# PwrAndBias.net
KiCad netlist of a schematic drawn in Altium Designer
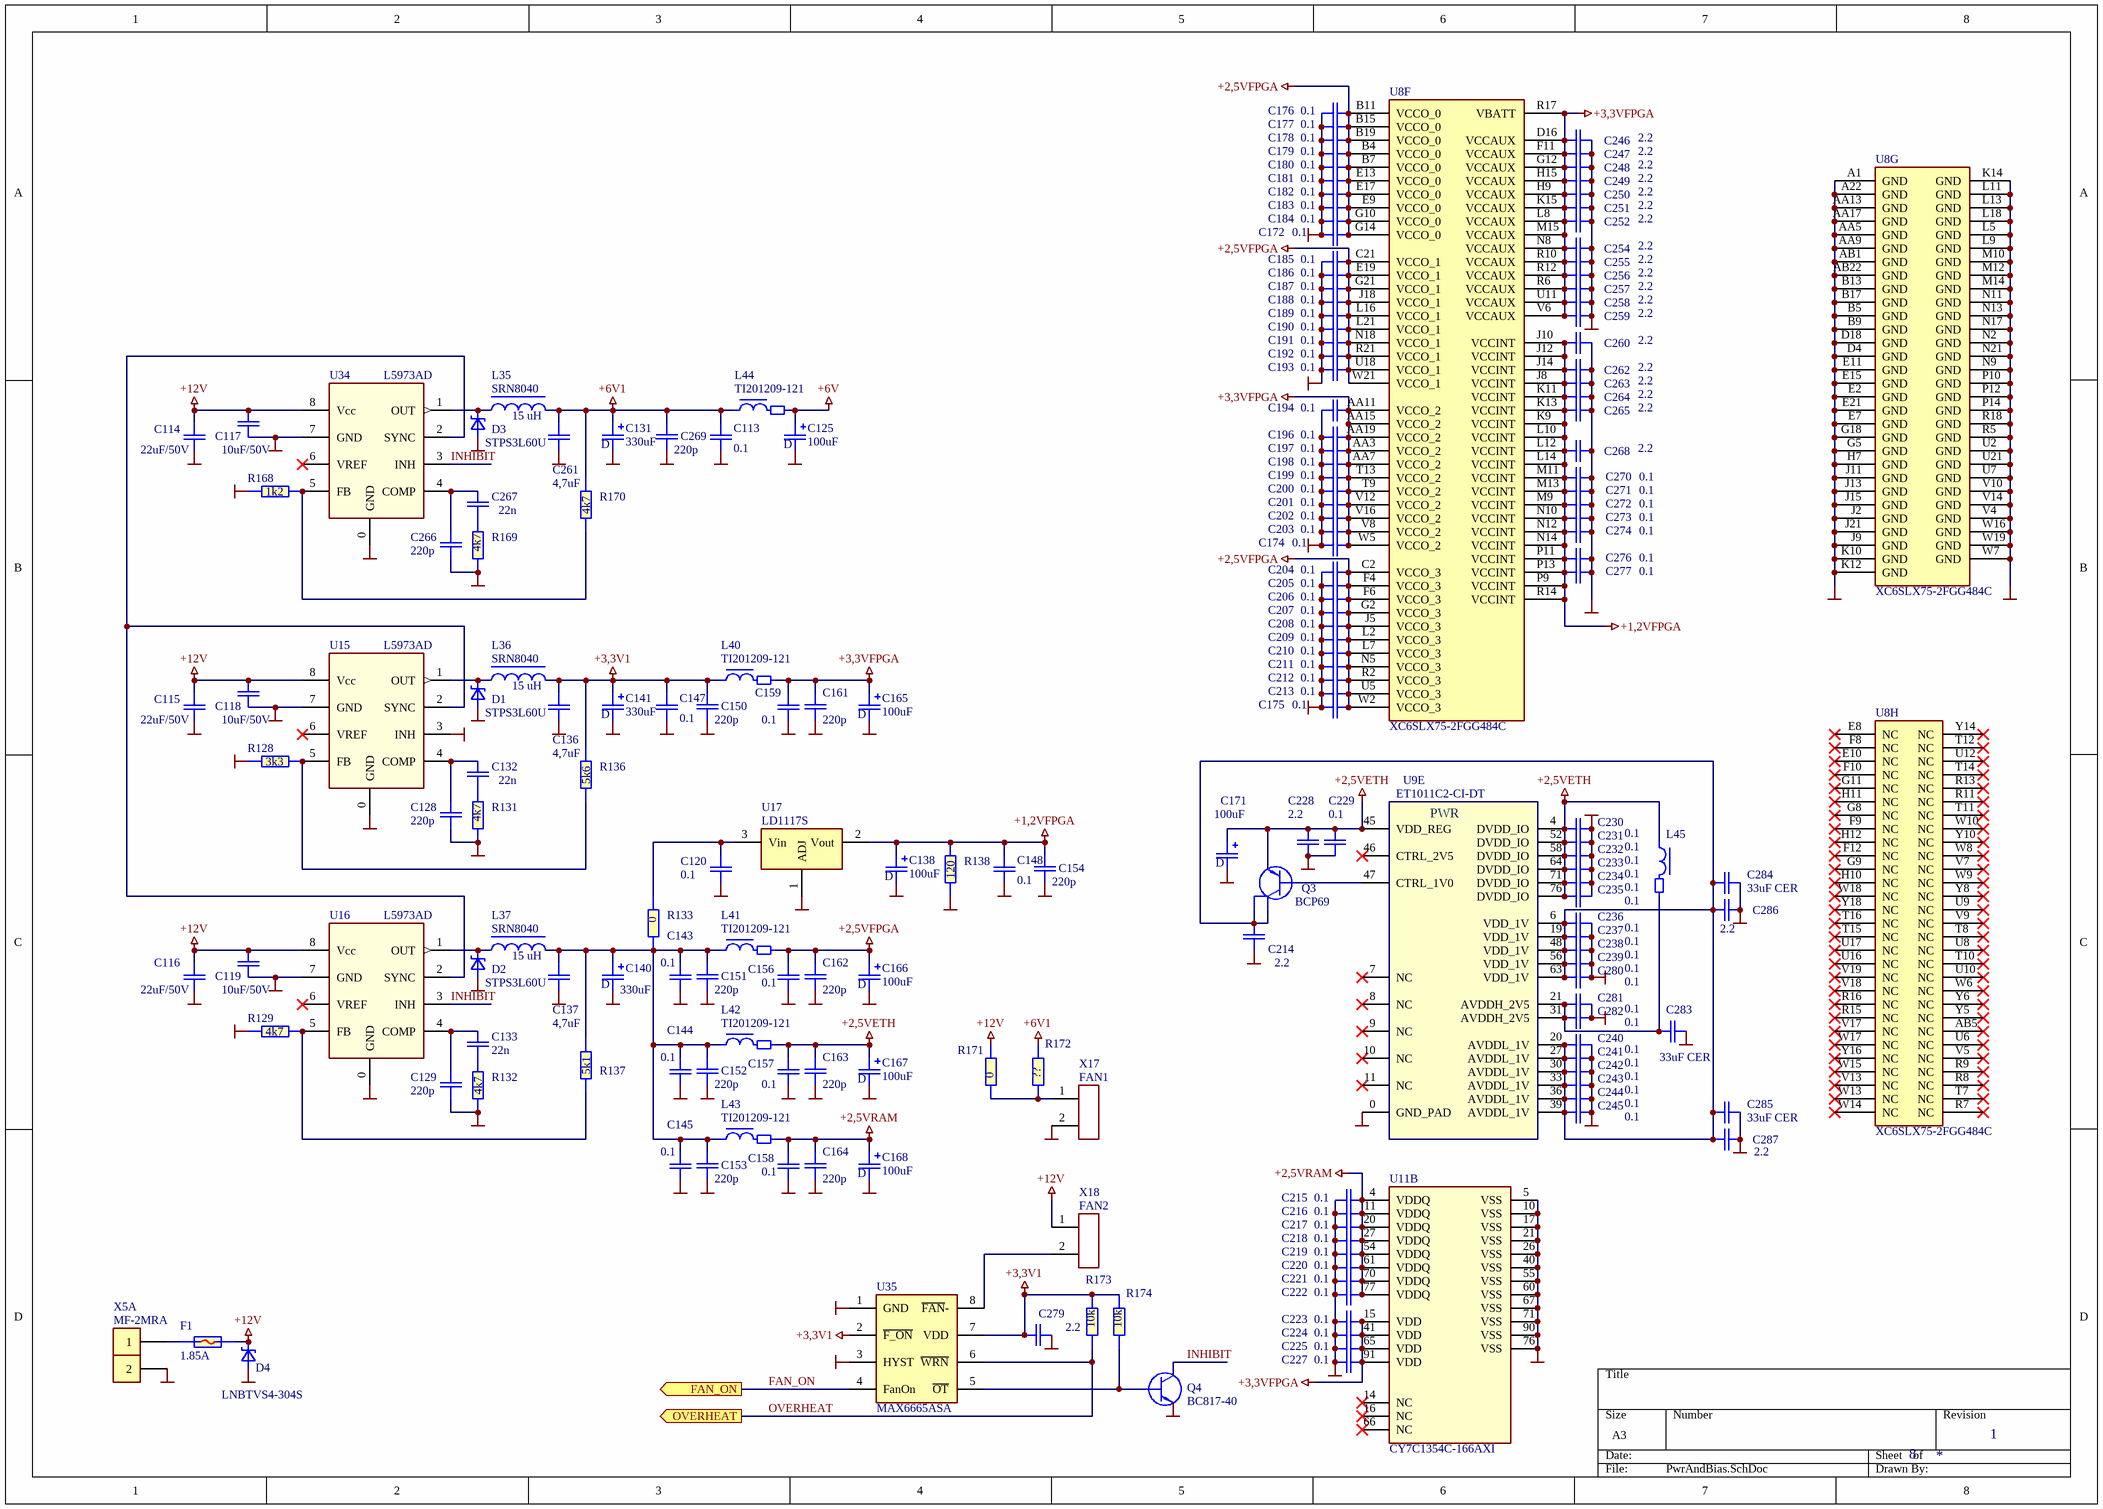
[diagram p0: PwrAndBias.SchDoc]

(export (version "E")
  (design (tool "Eeschema 10.0.6"))
  (components
    (comp (ref "C113")
      (value "0.1")
      (footprint "C0402-Phillips")
      (description "Конденсатор")
      (fields (field (name "MANUFACTURER") "MURATA") (field (name "TOLERANCE") "20%"))
      (libsource (lib "Capacitors") (part "C0402"))
    )
    (comp (ref "C114")
      (value "22uF/50V")
      (footprint "C2220")
      (description "Конденсатор")
      (fields (field (name "MANUFACTURER") "TDK"))
      (libsource (lib "Capacitors") (part "C2220"))
    )
    (comp (ref "C115")
      (value "22uF/50V")
      (footprint "C2220")
      (description "Конденсатор")
      (fields (field (name "MANUFACTURER") "TDK"))
      (libsource (lib "Capacitors") (part "C2220"))
    )
    (comp (ref "C116")
      (value "22uF/50V")
      (footprint "C2220")
      (description "Конденсатор")
      (fields (field (name "MANUFACTURER") "TDK"))
      (libsource (lib "Capacitors") (part "C2220"))
    )
    (comp (ref "C117")
      (value "10uF/50V")
      (footprint "C1210_H2,5")
      (description "Конденсатор")
      (fields (field (name "MANUFACTURER") "TAIYO YUDEN") (field (name "TOLERANCE") "20%"))
      (libsource (lib "Andy") (part "C1210_H2,5"))
    )
    (comp (ref "C118")
      (value "10uF/50V")
      (footprint "C1210_H2,5")
      (description "Конденсатор")
      (fields (field (name "MANUFACTURER") "TAIYO YUDEN") (field (name "TOLERANCE") "20%"))
      (libsource (lib "Andy") (part "C1210_H2,5"))
    )
    (comp (ref "C119")
      (value "10uF/50V")
      (footprint "C1210_H2,5")
      (description "Конденсатор")
      (fields (field (name "MANUFACTURER") "TAIYO YUDEN") (field (name "TOLERANCE") "20%"))
      (libsource (lib "Andy") (part "C1210_H2,5"))
    )
    (comp (ref "C120")
      (value "0.1")
      (footprint "C0402-Phillips")
      (description "Конденсатор")
      (fields (field (name "MANUFACTURER") "MURATA") (field (name "TOLERANCE") "20%"))
      (libsource (lib "Capacitors") (part "C0402"))
    )
    (comp (ref "C125")
      (value "100uF")
      (footprint "cd7343")
      (description "Конденсатор")
      (fields (field (name "MANUFACTURER") "SPRAGUE"))
      (libsource (lib "altium-import") (part "root_0_CD7343_"))
    )
    (comp (ref "C128")
      (value "220p")
      (footprint "C0603-PHILLIPS")
      (description "Конденсатор")
      (fields (field (name "MANUFACTURER") "MURATA") (field (name "TOLERANCE") "20%"))
      (libsource (lib "altium-import") (part "root_0_C0603_"))
    )
    (comp (ref "C129")
      (value "220p")
      (footprint "C0603-PHILLIPS")
      (description "Конденсатор")
      (fields (field (name "MANUFACTURER") "MURATA") (field (name "TOLERANCE") "20%"))
      (libsource (lib "altium-import") (part "root_0_C0603_"))
    )
    (comp (ref "C131")
      (value "330uF")
      (footprint "cd7343")
      (description "Конденсатор")
      (fields (field (name "MANUFACTURER") "Kemet"))
      (libsource (lib "altium-import") (part "root_0_CD7343_"))
    )
    (comp (ref "C132")
      (value "22n")
      (footprint "C0603-PHILLIPS")
      (description "Конденсатор")
      (fields (field (name "MANUFACTURER") "MURATA") (field (name "TOLERANCE") "20%"))
      (libsource (lib "altium-import") (part "root_0_C0603_"))
    )
    (comp (ref "C133")
      (value "22n")
      (footprint "C0603-PHILLIPS")
      (description "Конденсатор")
      (fields (field (name "MANUFACTURER") "MURATA") (field (name "TOLERANCE") "20%"))
      (libsource (lib "altium-import") (part "root_0_C0603_"))
    )
    (comp (ref "C136")
      (value "4,7uF")
      (footprint "c1206")
      (description "Конденсатор")
      (fields (field (name "MANUFACTURER") "Taiyo Yuden") (field (name "TOLERANCE") "10%"))
      (libsource (lib "altium-import") (part "root_0_C1206_"))
    )
    (comp (ref "C137")
      (value "4,7uF")
      (footprint "c1206")
      (description "Конденсатор")
      (fields (field (name "MANUFACTURER") "Taiyo Yuden") (field (name "TOLERANCE") "10%"))
      (libsource (lib "altium-import") (part "root_0_C1206_"))
    )
    (comp (ref "C138")
      (value "100uF")
      (footprint "cd7343")
      (description "Конденсатор")
      (fields (field (name "MANUFACTURER") "SPRAGUE"))
      (libsource (lib "altium-import") (part "root_0_CD7343_"))
    )
    (comp (ref "C140")
      (value "330uF")
      (footprint "cd7343")
      (description "Конденсатор")
      (fields (field (name "MANUFACTURER") "Kemet"))
      (libsource (lib "altium-import") (part "root_0_CD7343_"))
    )
    (comp (ref "C141")
      (value "330uF")
      (footprint "cd7343")
      (description "Конденсатор")
      (fields (field (name "MANUFACTURER") "Kemet"))
      (libsource (lib "altium-import") (part "root_0_CD7343_"))
    )
    (comp (ref "C143")
      (value "0.1")
      (footprint "C0402-Phillips")
      (description "Конденсатор")
      (fields (field (name "MANUFACTURER") "MURATA") (field (name "TOLERANCE") "20%"))
      (libsource (lib "Capacitors") (part "C0402"))
    )
    (comp (ref "C144")
      (value "0.1")
      (footprint "C0402-Phillips")
      (description "Конденсатор")
      (fields (field (name "MANUFACTURER") "MURATA") (field (name "TOLERANCE") "20%"))
      (libsource (lib "Capacitors") (part "C0402"))
    )
    (comp (ref "C145")
      (value "0.1")
      (footprint "C0402-Phillips")
      (description "Конденсатор")
      (fields (field (name "MANUFACTURER") "MURATA") (field (name "TOLERANCE") "20%"))
      (libsource (lib "Capacitors") (part "C0402"))
    )
    (comp (ref "C147")
      (value "0.1")
      (footprint "C0402-Phillips")
      (description "Конденсатор")
      (fields (field (name "MANUFACTURER") "MURATA") (field (name "TOLERANCE") "20%"))
      (libsource (lib "Capacitors") (part "C0402"))
    )
    (comp (ref "C148")
      (value "0.1")
      (footprint "C0402-Phillips")
      (description "Конденсатор")
      (fields (field (name "MANUFACTURER") "MURATA") (field (name "TOLERANCE") "20%"))
      (libsource (lib "Capacitors") (part "C0402"))
    )
    (comp (ref "C150")
      (value "220p")
      (footprint "C0603-PHILLIPS")
      (description "Конденсатор")
      (fields (field (name "MANUFACTURER") "MURATA") (field (name "TOLERANCE") "20%"))
      (libsource (lib "altium-import") (part "root_0_C0603_"))
    )
    (comp (ref "C151")
      (value "220p")
      (footprint "C0603-PHILLIPS")
      (description "Конденсатор")
      (fields (field (name "MANUFACTURER") "MURATA") (field (name "TOLERANCE") "20%"))
      (libsource (lib "altium-import") (part "root_0_C0603_"))
    )
    (comp (ref "C152")
      (value "220p")
      (footprint "C0603-PHILLIPS")
      (description "Конденсатор")
      (fields (field (name "MANUFACTURER") "MURATA") (field (name "TOLERANCE") "20%"))
      (libsource (lib "altium-import") (part "root_0_C0603_"))
    )
    (comp (ref "C153")
      (value "220p")
      (footprint "C0603-PHILLIPS")
      (description "Конденсатор")
      (fields (field (name "MANUFACTURER") "MURATA") (field (name "TOLERANCE") "20%"))
      (libsource (lib "altium-import") (part "root_0_C0603_"))
    )
    (comp (ref "C154")
      (value "220p")
      (footprint "C0603-PHILLIPS")
      (description "Конденсатор")
      (fields (field (name "MANUFACTURER") "MURATA") (field (name "TOLERANCE") "20%"))
      (libsource (lib "altium-import") (part "root_0_C0603_"))
    )
    (comp (ref "C156")
      (value "0.1")
      (footprint "C0402-Phillips")
      (description "Конденсатор")
      (fields (field (name "MANUFACTURER") "MURATA") (field (name "TOLERANCE") "20%"))
      (libsource (lib "Capacitors") (part "C0402"))
    )
    (comp (ref "C157")
      (value "0.1")
      (footprint "C0402-Phillips")
      (description "Конденсатор")
      (fields (field (name "MANUFACTURER") "MURATA") (field (name "TOLERANCE") "20%"))
      (libsource (lib "Capacitors") (part "C0402"))
    )
    (comp (ref "C158")
      (value "0.1")
      (footprint "C0402-Phillips")
      (description "Конденсатор")
      (fields (field (name "MANUFACTURER") "MURATA") (field (name "TOLERANCE") "20%"))
      (libsource (lib "Capacitors") (part "C0402"))
    )
    (comp (ref "C159")
      (value "0.1")
      (footprint "C0402-Phillips")
      (description "Конденсатор")
      (fields (field (name "MANUFACTURER") "MURATA") (field (name "TOLERANCE") "20%"))
      (libsource (lib "Capacitors") (part "C0402"))
    )
    (comp (ref "C161")
      (value "220p")
      (footprint "C0603-PHILLIPS")
      (description "Конденсатор")
      (fields (field (name "MANUFACTURER") "MURATA") (field (name "TOLERANCE") "20%"))
      (libsource (lib "altium-import") (part "root_0_C0603_"))
    )
    (comp (ref "C162")
      (value "220p")
      (footprint "C0603-PHILLIPS")
      (description "Конденсатор")
      (fields (field (name "MANUFACTURER") "MURATA") (field (name "TOLERANCE") "20%"))
      (libsource (lib "altium-import") (part "root_0_C0603_"))
    )
    (comp (ref "C163")
      (value "220p")
      (footprint "C0603-PHILLIPS")
      (description "Конденсатор")
      (fields (field (name "MANUFACTURER") "MURATA") (field (name "TOLERANCE") "20%"))
      (libsource (lib "altium-import") (part "root_0_C0603_"))
    )
    (comp (ref "C164")
      (value "220p")
      (footprint "C0603-PHILLIPS")
      (description "Конденсатор")
      (fields (field (name "MANUFACTURER") "MURATA") (field (name "TOLERANCE") "20%"))
      (libsource (lib "altium-import") (part "root_0_C0603_"))
    )
    (comp (ref "C165")
      (value "100uF")
      (footprint "cd7343")
      (description "Конденсатор")
      (fields (field (name "MANUFACTURER") "SPRAGUE"))
      (libsource (lib "altium-import") (part "root_0_CD7343_"))
    )
    (comp (ref "C166")
      (value "100uF")
      (footprint "cd7343")
      (description "Конденсатор")
      (fields (field (name "MANUFACTURER") "SPRAGUE"))
      (libsource (lib "altium-import") (part "root_0_CD7343_"))
    )
    (comp (ref "C167")
      (value "100uF")
      (footprint "cd7343")
      (description "Конденсатор")
      (fields (field (name "MANUFACTURER") "SPRAGUE"))
      (libsource (lib "altium-import") (part "root_0_CD7343_"))
    )
    (comp (ref "C168")
      (value "100uF")
      (footprint "cd7343")
      (description "Конденсатор")
      (fields (field (name "MANUFACTURER") "SPRAGUE"))
      (libsource (lib "altium-import") (part "root_0_CD7343_"))
    )
    (comp (ref "C171")
      (value "100uF")
      (footprint "cd7343")
      (description "Конденсатор")
      (fields (field (name "MANUFACTURER") "SPRAGUE"))
      (libsource (lib "altium-import") (part "root_0_CD7343_"))
    )
    (comp (ref "C172")
      (value "0.1")
      (footprint "C0402-cirq")
      (description "Конденсатор")
      (fields (field (name "MANUFACTURER") "MURATA") (field (name "TOLERANCE") "20%"))
      (libsource (lib "Capacitors") (part "C0402"))
    )
    (comp (ref "C174")
      (value "0.1")
      (footprint "C0402-cirq")
      (description "Конденсатор")
      (fields (field (name "MANUFACTURER") "MURATA") (field (name "TOLERANCE") "20%"))
      (libsource (lib "Capacitors") (part "C0402"))
    )
    (comp (ref "C175")
      (value "0.1")
      (footprint "C0402-cirq")
      (description "Конденсатор")
      (fields (field (name "MANUFACTURER") "MURATA") (field (name "TOLERANCE") "20%"))
      (libsource (lib "Capacitors") (part "C0402"))
    )
    (comp (ref "C176")
      (value "0.1")
      (footprint "C0402-cirq")
      (description "Конденсатор")
      (fields (field (name "MANUFACTURER") "MURATA") (field (name "TOLERANCE") "20%"))
      (libsource (lib "Capacitors") (part "C0402"))
    )
    (comp (ref "C177")
      (value "0.1")
      (footprint "C0402-cirq")
      (description "Конденсатор")
      (fields (field (name "MANUFACTURER") "MURATA") (field (name "TOLERANCE") "20%"))
      (libsource (lib "Capacitors") (part "C0402"))
    )
    (comp (ref "C178")
      (value "0.1")
      (footprint "C0402-cirq")
      (description "Конденсатор")
      (fields (field (name "MANUFACTURER") "MURATA") (field (name "TOLERANCE") "20%"))
      (libsource (lib "Capacitors") (part "C0402"))
    )
    (comp (ref "C179")
      (value "0.1")
      (footprint "C0402-cirq")
      (description "Конденсатор")
      (fields (field (name "MANUFACTURER") "MURATA") (field (name "TOLERANCE") "20%"))
      (libsource (lib "Capacitors") (part "C0402"))
    )
    (comp (ref "C180")
      (value "0.1")
      (footprint "C0402-cirq")
      (description "Конденсатор")
      (fields (field (name "MANUFACTURER") "MURATA") (field (name "TOLERANCE") "20%"))
      (libsource (lib "Capacitors") (part "C0402"))
    )
    (comp (ref "C181")
      (value "0.1")
      (footprint "C0402-cirq")
      (description "Конденсатор")
      (fields (field (name "MANUFACTURER") "MURATA") (field (name "TOLERANCE") "20%"))
      (libsource (lib "Capacitors") (part "C0402"))
    )
    (comp (ref "C182")
      (value "0.1")
      (footprint "C0402-cirq")
      (description "Конденсатор")
      (fields (field (name "MANUFACTURER") "MURATA") (field (name "TOLERANCE") "20%"))
      (libsource (lib "Capacitors") (part "C0402"))
    )
    (comp (ref "C183")
      (value "0.1")
      (footprint "C0402-cirq")
      (description "Конденсатор")
      (fields (field (name "MANUFACTURER") "MURATA") (field (name "TOLERANCE") "20%"))
      (libsource (lib "Capacitors") (part "C0402"))
    )
    (comp (ref "C184")
      (value "0.1")
      (footprint "C0402-cirq")
      (description "Конденсатор")
      (fields (field (name "MANUFACTURER") "MURATA") (field (name "TOLERANCE") "20%"))
      (libsource (lib "Capacitors") (part "C0402"))
    )
    (comp (ref "C185")
      (value "0.1")
      (footprint "C0402-cirq")
      (description "Конденсатор")
      (fields (field (name "MANUFACTURER") "MURATA") (field (name "TOLERANCE") "20%"))
      (libsource (lib "Capacitors") (part "C0402"))
    )
    (comp (ref "C186")
      (value "0.1")
      (footprint "C0402-cirq")
      (description "Конденсатор")
      (fields (field (name "MANUFACTURER") "MURATA") (field (name "TOLERANCE") "20%"))
      (libsource (lib "Capacitors") (part "C0402"))
    )
    (comp (ref "C187")
      (value "0.1")
      (footprint "C0402-cirq")
      (description "Конденсатор")
      (fields (field (name "MANUFACTURER") "MURATA") (field (name "TOLERANCE") "20%"))
      (libsource (lib "Capacitors") (part "C0402"))
    )
    (comp (ref "C188")
      (value "0.1")
      (footprint "C0402-cirq")
      (description "Конденсатор")
      (fields (field (name "MANUFACTURER") "MURATA") (field (name "TOLERANCE") "20%"))
      (libsource (lib "Capacitors") (part "C0402"))
    )
    (comp (ref "C189")
      (value "0.1")
      (footprint "C0402-cirq")
      (description "Конденсатор")
      (fields (field (name "MANUFACTURER") "MURATA") (field (name "TOLERANCE") "20%"))
      (libsource (lib "Capacitors") (part "C0402"))
    )
    (comp (ref "C190")
      (value "0.1")
      (footprint "C0402-cirq")
      (description "Конденсатор")
      (fields (field (name "MANUFACTURER") "MURATA") (field (name "TOLERANCE") "20%"))
      (libsource (lib "Capacitors") (part "C0402"))
    )
    (comp (ref "C191")
      (value "0.1")
      (footprint "C0402-cirq")
      (description "Конденсатор")
      (fields (field (name "MANUFACTURER") "MURATA") (field (name "TOLERANCE") "20%"))
      (libsource (lib "Capacitors") (part "C0402"))
    )
    (comp (ref "C192")
      (value "0.1")
      (footprint "C0402-cirq")
      (description "Конденсатор")
      (fields (field (name "MANUFACTURER") "MURATA") (field (name "TOLERANCE") "20%"))
      (libsource (lib "Capacitors") (part "C0402"))
    )
    (comp (ref "C193")
      (value "0.1")
      (footprint "C0402-cirq")
      (description "Конденсатор")
      (fields (field (name "MANUFACTURER") "MURATA") (field (name "TOLERANCE") "20%"))
      (libsource (lib "Capacitors") (part "C0402"))
    )
    (comp (ref "C194")
      (value "0.1")
      (footprint "C0402-cirq")
      (description "Конденсатор")
      (fields (field (name "MANUFACTURER") "MURATA") (field (name "TOLERANCE") "20%"))
      (libsource (lib "Capacitors") (part "C0402"))
    )
    (comp (ref "C196")
      (value "0.1")
      (footprint "C0402-cirq")
      (description "Конденсатор")
      (fields (field (name "MANUFACTURER") "MURATA") (field (name "TOLERANCE") "20%"))
      (libsource (lib "Capacitors") (part "C0402"))
    )
    (comp (ref "C197")
      (value "0.1")
      (footprint "C0402-cirq")
      (description "Конденсатор")
      (fields (field (name "MANUFACTURER") "MURATA") (field (name "TOLERANCE") "20%"))
      (libsource (lib "Capacitors") (part "C0402"))
    )
    (comp (ref "C198")
      (value "0.1")
      (footprint "C0402-cirq")
      (description "Конденсатор")
      (fields (field (name "MANUFACTURER") "MURATA") (field (name "TOLERANCE") "20%"))
      (libsource (lib "Capacitors") (part "C0402"))
    )
    (comp (ref "C199")
      (value "0.1")
      (footprint "C0402-cirq")
      (description "Конденсатор")
      (fields (field (name "MANUFACTURER") "MURATA") (field (name "TOLERANCE") "20%"))
      (libsource (lib "Capacitors") (part "C0402"))
    )
    (comp (ref "C200")
      (value "0.1")
      (footprint "C0402-cirq")
      (description "Конденсатор")
      (fields (field (name "MANUFACTURER") "MURATA") (field (name "TOLERANCE") "20%"))
      (libsource (lib "Capacitors") (part "C0402"))
    )
    (comp (ref "C201")
      (value "0.1")
      (footprint "C0402-cirq")
      (description "Конденсатор")
      (fields (field (name "MANUFACTURER") "MURATA") (field (name "TOLERANCE") "20%"))
      (libsource (lib "Capacitors") (part "C0402"))
    )
    (comp (ref "C202")
      (value "0.1")
      (footprint "C0402-cirq")
      (description "Конденсатор")
      (fields (field (name "MANUFACTURER") "MURATA") (field (name "TOLERANCE") "20%"))
      (libsource (lib "Capacitors") (part "C0402"))
    )
    (comp (ref "C203")
      (value "0.1")
      (footprint "C0402-cirq")
      (description "Конденсатор")
      (fields (field (name "MANUFACTURER") "MURATA") (field (name "TOLERANCE") "20%"))
      (libsource (lib "Capacitors") (part "C0402"))
    )
    (comp (ref "C204")
      (value "0.1")
      (footprint "C0402-cirq")
      (description "Конденсатор")
      (fields (field (name "MANUFACTURER") "MURATA") (field (name "TOLERANCE") "20%"))
      (libsource (lib "Capacitors") (part "C0402"))
    )
    (comp (ref "C205")
      (value "0.1")
      (footprint "C0402-cirq")
      (description "Конденсатор")
      (fields (field (name "MANUFACTURER") "MURATA") (field (name "TOLERANCE") "20%"))
      (libsource (lib "Capacitors") (part "C0402"))
    )
    (comp (ref "C206")
      (value "0.1")
      (footprint "C0402-cirq")
      (description "Конденсатор")
      (fields (field (name "MANUFACTURER") "MURATA") (field (name "TOLERANCE") "20%"))
      (libsource (lib "Capacitors") (part "C0402"))
    )
    (comp (ref "C207")
      (value "0.1")
      (footprint "C0402-cirq")
      (description "Конденсатор")
      (fields (field (name "MANUFACTURER") "MURATA") (field (name "TOLERANCE") "20%"))
      (libsource (lib "Capacitors") (part "C0402"))
    )
    (comp (ref "C208")
      (value "0.1")
      (footprint "C0402-cirq")
      (description "Конденсатор")
      (fields (field (name "MANUFACTURER") "MURATA") (field (name "TOLERANCE") "20%"))
      (libsource (lib "Capacitors") (part "C0402"))
    )
    (comp (ref "C209")
      (value "0.1")
      (footprint "C0402-cirq")
      (description "Конденсатор")
      (fields (field (name "MANUFACTURER") "MURATA") (field (name "TOLERANCE") "20%"))
      (libsource (lib "Capacitors") (part "C0402"))
    )
    (comp (ref "C210")
      (value "0.1")
      (footprint "C0402-cirq")
      (description "Конденсатор")
      (fields (field (name "MANUFACTURER") "MURATA") (field (name "TOLERANCE") "20%"))
      (libsource (lib "Capacitors") (part "C0402"))
    )
    (comp (ref "C211")
      (value "0.1")
      (footprint "C0402-cirq")
      (description "Конденсатор")
      (fields (field (name "MANUFACTURER") "MURATA") (field (name "TOLERANCE") "20%"))
      (libsource (lib "Capacitors") (part "C0402"))
    )
    (comp (ref "C212")
      (value "0.1")
      (footprint "C0402-cirq")
      (description "Конденсатор")
      (fields (field (name "MANUFACTURER") "MURATA") (field (name "TOLERANCE") "20%"))
      (libsource (lib "Capacitors") (part "C0402"))
    )
    (comp (ref "C213")
      (value "0.1")
      (footprint "C0402-cirq")
      (description "Конденсатор")
      (fields (field (name "MANUFACTURER") "MURATA") (field (name "TOLERANCE") "20%"))
      (libsource (lib "Capacitors") (part "C0402"))
    )
    (comp (ref "C214")
      (value "2.2")
      (footprint "C0402-Phillips")
      (description "Конденсатор")
      (fields (field (name "MANUFACTURER") "MURATA") (field (name "TOLERANCE") "20%"))
      (libsource (lib "Capacitors") (part "C0402"))
    )
    (comp (ref "C215")
      (value "0.1")
      (footprint "C0402-Phillips")
      (description "Конденсатор")
      (fields (field (name "MANUFACTURER") "MURATA") (field (name "TOLERANCE") "20%"))
      (libsource (lib "Capacitors") (part "C0402"))
    )
    (comp (ref "C216")
      (value "0.1")
      (footprint "C0402-Phillips")
      (description "Конденсатор")
      (fields (field (name "MANUFACTURER") "MURATA") (field (name "TOLERANCE") "20%"))
      (libsource (lib "Capacitors") (part "C0402"))
    )
    (comp (ref "C217")
      (value "0.1")
      (footprint "C0402-Phillips")
      (description "Конденсатор")
      (fields (field (name "MANUFACTURER") "MURATA") (field (name "TOLERANCE") "20%"))
      (libsource (lib "Capacitors") (part "C0402"))
    )
    (comp (ref "C218")
      (value "0.1")
      (footprint "C0402-Phillips")
      (description "Конденсатор")
      (fields (field (name "MANUFACTURER") "MURATA") (field (name "TOLERANCE") "20%"))
      (libsource (lib "Capacitors") (part "C0402"))
    )
    (comp (ref "C219")
      (value "0.1")
      (footprint "C0402-Phillips")
      (description "Конденсатор")
      (fields (field (name "MANUFACTURER") "MURATA") (field (name "TOLERANCE") "20%"))
      (libsource (lib "Capacitors") (part "C0402"))
    )
    (comp (ref "C220")
      (value "0.1")
      (footprint "C0402-Phillips")
      (description "Конденсатор")
      (fields (field (name "MANUFACTURER") "MURATA") (field (name "TOLERANCE") "20%"))
      (libsource (lib "Capacitors") (part "C0402"))
    )
    (comp (ref "C221")
      (value "0.1")
      (footprint "C0402-Phillips")
      (description "Конденсатор")
      (fields (field (name "MANUFACTURER") "MURATA") (field (name "TOLERANCE") "20%"))
      (libsource (lib "Capacitors") (part "C0402"))
    )
    (comp (ref "C222")
      (value "0.1")
      (footprint "C0402-Phillips")
      (description "Конденсатор")
      (fields (field (name "MANUFACTURER") "MURATA") (field (name "TOLERANCE") "20%"))
      (libsource (lib "Capacitors") (part "C0402"))
    )
    (comp (ref "C223")
      (value "0.1")
      (footprint "C0402-Phillips")
      (description "Конденсатор")
      (fields (field (name "MANUFACTURER") "MURATA") (field (name "TOLERANCE") "20%"))
      (libsource (lib "Capacitors") (part "C0402"))
    )
    (comp (ref "C224")
      (value "0.1")
      (footprint "C0402-Phillips")
      (description "Конденсатор")
      (fields (field (name "MANUFACTURER") "MURATA") (field (name "TOLERANCE") "20%"))
      (libsource (lib "Capacitors") (part "C0402"))
    )
    (comp (ref "C225")
      (value "0.1")
      (footprint "C0402-Phillips")
      (description "Конденсатор")
      (fields (field (name "MANUFACTURER") "MURATA") (field (name "TOLERANCE") "20%"))
      (libsource (lib "Capacitors") (part "C0402"))
    )
    (comp (ref "C227")
      (value "0.1")
      (footprint "C0402-Phillips")
      (description "Конденсатор")
      (fields (field (name "MANUFACTURER") "MURATA") (field (name "TOLERANCE") "20%"))
      (libsource (lib "Capacitors") (part "C0402"))
    )
    (comp (ref "C228")
      (value "2.2")
      (footprint "C0402-Phillips")
      (description "Конденсатор")
      (fields (field (name "MANUFACTURER") "MURATA") (field (name "TOLERANCE") "20%"))
      (libsource (lib "Capacitors") (part "C0402"))
    )
    (comp (ref "C229")
      (value "0.1")
      (footprint "C0402-Phillips")
      (description "Конденсатор")
      (fields (field (name "MANUFACTURER") "MURATA") (field (name "TOLERANCE") "20%"))
      (libsource (lib "Capacitors") (part "C0402"))
    )
    (comp (ref "C230")
      (value "0.1")
      (footprint "C0402-Phillips")
      (description "Конденсатор")
      (fields (field (name "MANUFACTURER") "MURATA") (field (name "TOLERANCE") "20%"))
      (libsource (lib "Capacitors") (part "C0402"))
    )
    (comp (ref "C231")
      (value "0.1")
      (footprint "C0402-Phillips")
      (description "Конденсатор")
      (fields (field (name "MANUFACTURER") "MURATA") (field (name "TOLERANCE") "20%"))
      (libsource (lib "Capacitors") (part "C0402"))
    )
    (comp (ref "C232")
      (value "0.1")
      (footprint "C0402-Phillips")
      (description "Конденсатор")
      (fields (field (name "MANUFACTURER") "MURATA") (field (name "TOLERANCE") "20%"))
      (libsource (lib "Capacitors") (part "C0402"))
    )
    (comp (ref "C233")
      (value "0.1")
      (footprint "C0402-Phillips")
      (description "Конденсатор")
      (fields (field (name "MANUFACTURER") "MURATA") (field (name "TOLERANCE") "20%"))
      (libsource (lib "Capacitors") (part "C0402"))
    )
    (comp (ref "C234")
      (value "0.1")
      (footprint "C0402-Phillips")
      (description "Конденсатор")
      (fields (field (name "MANUFACTURER") "MURATA") (field (name "TOLERANCE") "20%"))
      (libsource (lib "Capacitors") (part "C0402"))
    )
    (comp (ref "C235")
      (value "0.1")
      (footprint "C0402-Phillips")
      (description "Конденсатор")
      (fields (field (name "MANUFACTURER") "MURATA") (field (name "TOLERANCE") "20%"))
      (libsource (lib "Capacitors") (part "C0402"))
    )
    (comp (ref "C236")
      (value "0.1")
      (footprint "C0402-Phillips")
      (description "Конденсатор")
      (fields (field (name "MANUFACTURER") "MURATA") (field (name "TOLERANCE") "20%"))
      (libsource (lib "Capacitors") (part "C0402"))
    )
    (comp (ref "C237")
      (value "0.1")
      (footprint "C0402-Phillips")
      (description "Конденсатор")
      (fields (field (name "MANUFACTURER") "MURATA") (field (name "TOLERANCE") "20%"))
      (libsource (lib "Capacitors") (part "C0402"))
    )
    (comp (ref "C238")
      (value "0.1")
      (footprint "C0402-Phillips")
      (description "Конденсатор")
      (fields (field (name "MANUFACTURER") "MURATA") (field (name "TOLERANCE") "20%"))
      (libsource (lib "Capacitors") (part "C0402"))
    )
    (comp (ref "C239")
      (value "0.1")
      (footprint "C0402-Phillips")
      (description "Конденсатор")
      (fields (field (name "MANUFACTURER") "MURATA") (field (name "TOLERANCE") "20%"))
      (libsource (lib "Capacitors") (part "C0402"))
    )
    (comp (ref "C240")
      (value "0.1")
      (footprint "C0402-Phillips")
      (description "Конденсатор")
      (fields (field (name "MANUFACTURER") "MURATA") (field (name "TOLERANCE") "20%"))
      (libsource (lib "Capacitors") (part "C0402"))
    )
    (comp (ref "C241")
      (value "0.1")
      (footprint "C0402-Phillips")
      (description "Конденсатор")
      (fields (field (name "MANUFACTURER") "MURATA") (field (name "TOLERANCE") "20%"))
      (libsource (lib "Capacitors") (part "C0402"))
    )
    (comp (ref "C242")
      (value "0.1")
      (footprint "C0402-Phillips")
      (description "Конденсатор")
      (fields (field (name "MANUFACTURER") "MURATA") (field (name "TOLERANCE") "20%"))
      (libsource (lib "Capacitors") (part "C0402"))
    )
    (comp (ref "C243")
      (value "0.1")
      (footprint "C0402-Phillips")
      (description "Конденсатор")
      (fields (field (name "MANUFACTURER") "MURATA") (field (name "TOLERANCE") "20%"))
      (libsource (lib "Capacitors") (part "C0402"))
    )
    (comp (ref "C244")
      (value "0.1")
      (footprint "C0402-Phillips")
      (description "Конденсатор")
      (fields (field (name "MANUFACTURER") "MURATA") (field (name "TOLERANCE") "20%"))
      (libsource (lib "Capacitors") (part "C0402"))
    )
    (comp (ref "C245")
      (value "0.1")
      (footprint "C0402-Phillips")
      (description "Конденсатор")
      (fields (field (name "MANUFACTURER") "MURATA") (field (name "TOLERANCE") "20%"))
      (libsource (lib "Capacitors") (part "C0402"))
    )
    (comp (ref "C246")
      (value "2.2")
      (footprint "C0402-cirq")
      (description "Конденсатор")
      (fields (field (name "MANUFACTURER") "MURATA") (field (name "TOLERANCE") "20%"))
      (libsource (lib "Capacitors") (part "C0402"))
    )
    (comp (ref "C247")
      (value "2.2")
      (footprint "C0402-cirq")
      (description "Конденсатор")
      (fields (field (name "MANUFACTURER") "MURATA") (field (name "TOLERANCE") "20%"))
      (libsource (lib "Capacitors") (part "C0402"))
    )
    (comp (ref "C248")
      (value "2.2")
      (footprint "C0402-cirq")
      (description "Конденсатор")
      (fields (field (name "MANUFACTURER") "MURATA") (field (name "TOLERANCE") "20%"))
      (libsource (lib "Capacitors") (part "C0402"))
    )
    (comp (ref "C249")
      (value "2.2")
      (footprint "C0402-cirq")
      (description "Конденсатор")
      (fields (field (name "MANUFACTURER") "MURATA") (field (name "TOLERANCE") "20%"))
      (libsource (lib "Capacitors") (part "C0402"))
    )
    (comp (ref "C250")
      (value "2.2")
      (footprint "C0402-cirq")
      (description "Конденсатор")
      (fields (field (name "MANUFACTURER") "MURATA") (field (name "TOLERANCE") "20%"))
      (libsource (lib "Capacitors") (part "C0402"))
    )
    (comp (ref "C251")
      (value "2.2")
      (footprint "C0402-cirq")
      (description "Конденсатор")
      (fields (field (name "MANUFACTURER") "MURATA") (field (name "TOLERANCE") "20%"))
      (libsource (lib "Capacitors") (part "C0402"))
    )
    (comp (ref "C252")
      (value "2.2")
      (footprint "C0402-cirq")
      (description "Конденсатор")
      (fields (field (name "MANUFACTURER") "MURATA") (field (name "TOLERANCE") "20%"))
      (libsource (lib "Capacitors") (part "C0402"))
    )
    (comp (ref "C254")
      (value "2.2")
      (footprint "C0402-cirq")
      (description "Конденсатор")
      (fields (field (name "MANUFACTURER") "MURATA") (field (name "TOLERANCE") "20%"))
      (libsource (lib "Capacitors") (part "C0402"))
    )
    (comp (ref "C255")
      (value "2.2")
      (footprint "C0402-cirq")
      (description "Конденсатор")
      (fields (field (name "MANUFACTURER") "MURATA") (field (name "TOLERANCE") "20%"))
      (libsource (lib "Capacitors") (part "C0402"))
    )
    (comp (ref "C256")
      (value "2.2")
      (footprint "C0402-cirq")
      (description "Конденсатор")
      (fields (field (name "MANUFACTURER") "MURATA") (field (name "TOLERANCE") "20%"))
      (libsource (lib "Capacitors") (part "C0402"))
    )
    (comp (ref "C257")
      (value "2.2")
      (footprint "C0402-cirq")
      (description "Конденсатор")
      (fields (field (name "MANUFACTURER") "MURATA") (field (name "TOLERANCE") "20%"))
      (libsource (lib "Capacitors") (part "C0402"))
    )
    (comp (ref "C258")
      (value "2.2")
      (footprint "C0402-cirq")
      (description "Конденсатор")
      (fields (field (name "MANUFACTURER") "MURATA") (field (name "TOLERANCE") "20%"))
      (libsource (lib "Capacitors") (part "C0402"))
    )
    (comp (ref "C259")
      (value "2.2")
      (footprint "C0402-cirq")
      (description "Конденсатор")
      (fields (field (name "MANUFACTURER") "MURATA") (field (name "TOLERANCE") "20%"))
      (libsource (lib "Capacitors") (part "C0402"))
    )
    (comp (ref "C260")
      (value "2.2")
      (footprint "C0402-cirq")
      (description "Конденсатор")
      (fields (field (name "MANUFACTURER") "MURATA") (field (name "TOLERANCE") "20%"))
      (libsource (lib "Capacitors") (part "C0402"))
    )
    (comp (ref "C261")
      (value "4,7uF")
      (footprint "c1206")
      (description "Конденсатор")
      (fields (field (name "MANUFACTURER") "Taiyo Yuden") (field (name "TOLERANCE") "10%"))
      (libsource (lib "altium-import") (part "root_0_C1206_"))
    )
    (comp (ref "C262")
      (value "2.2")
      (footprint "C0402-cirq")
      (description "Конденсатор")
      (fields (field (name "MANUFACTURER") "MURATA") (field (name "TOLERANCE") "20%"))
      (libsource (lib "Capacitors") (part "C0402"))
    )
    (comp (ref "C263")
      (value "2.2")
      (footprint "C0402-cirq")
      (description "Конденсатор")
      (fields (field (name "MANUFACTURER") "MURATA") (field (name "TOLERANCE") "20%"))
      (libsource (lib "Capacitors") (part "C0402"))
    )
    (comp (ref "C264")
      (value "2.2")
      (footprint "C0402-cirq")
      (description "Конденсатор")
      (fields (field (name "MANUFACTURER") "MURATA") (field (name "TOLERANCE") "20%"))
      (libsource (lib "Capacitors") (part "C0402"))
    )
    (comp (ref "C265")
      (value "2.2")
      (footprint "C0402-cirq")
      (description "Конденсатор")
      (fields (field (name "MANUFACTURER") "MURATA") (field (name "TOLERANCE") "20%"))
      (libsource (lib "Capacitors") (part "C0402"))
    )
    (comp (ref "C266")
      (value "220p")
      (footprint "C0603-PHILLIPS")
      (description "Конденсатор")
      (fields (field (name "MANUFACTURER") "MURATA") (field (name "TOLERANCE") "20%"))
      (libsource (lib "altium-import") (part "root_0_C0603_"))
    )
    (comp (ref "C267")
      (value "22n")
      (footprint "C0603-PHILLIPS")
      (description "Конденсатор")
      (fields (field (name "MANUFACTURER") "MURATA") (field (name "TOLERANCE") "20%"))
      (libsource (lib "altium-import") (part "root_0_C0603_"))
    )
    (comp (ref "C268")
      (value "2.2")
      (footprint "C0402-cirq")
      (description "Конденсатор")
      (fields (field (name "MANUFACTURER") "MURATA") (field (name "TOLERANCE") "20%"))
      (libsource (lib "Capacitors") (part "C0402"))
    )
    (comp (ref "C269")
      (value "220p")
      (footprint "C0603-PHILLIPS")
      (description "Конденсатор")
      (fields (field (name "MANUFACTURER") "MURATA") (field (name "TOLERANCE") "20%"))
      (libsource (lib "altium-import") (part "root_0_C0603_"))
    )
    (comp (ref "C270")
      (value "0.1")
      (footprint "C0402-cirq")
      (description "Конденсатор")
      (fields (field (name "MANUFACTURER") "MURATA") (field (name "TOLERANCE") "20%"))
      (libsource (lib "Capacitors") (part "C0402"))
    )
    (comp (ref "C271")
      (value "0.1")
      (footprint "C0402-cirq")
      (description "Конденсатор")
      (fields (field (name "MANUFACTURER") "MURATA") (field (name "TOLERANCE") "20%"))
      (libsource (lib "Capacitors") (part "C0402"))
    )
    (comp (ref "C272")
      (value "0.1")
      (footprint "C0402-cirq")
      (description "Конденсатор")
      (fields (field (name "MANUFACTURER") "MURATA") (field (name "TOLERANCE") "20%"))
      (libsource (lib "Capacitors") (part "C0402"))
    )
    (comp (ref "C273")
      (value "0.1")
      (footprint "C0402-cirq")
      (description "Конденсатор")
      (fields (field (name "MANUFACTURER") "MURATA") (field (name "TOLERANCE") "20%"))
      (libsource (lib "Capacitors") (part "C0402"))
    )
    (comp (ref "C274")
      (value "0.1")
      (footprint "C0402-cirq")
      (description "Конденсатор")
      (fields (field (name "MANUFACTURER") "MURATA") (field (name "TOLERANCE") "20%"))
      (libsource (lib "Capacitors") (part "C0402"))
    )
    (comp (ref "C276")
      (value "0.1")
      (footprint "C0402-cirq")
      (description "Конденсатор")
      (fields (field (name "MANUFACTURER") "MURATA") (field (name "TOLERANCE") "20%"))
      (libsource (lib "Capacitors") (part "C0402"))
    )
    (comp (ref "C277")
      (value "0.1")
      (footprint "C0402-cirq")
      (description "Конденсатор")
      (fields (field (name "MANUFACTURER") "MURATA") (field (name "TOLERANCE") "20%"))
      (libsource (lib "Capacitors") (part "C0402"))
    )
    (comp (ref "C279")
      (value "2.2")
      (footprint "C0402-Phillips")
      (description "Конденсатор")
      (fields (field (name "MANUFACTURER") "MURATA") (field (name "TOLERANCE") "20%"))
      (libsource (lib "Capacitors") (part "C0402"))
    )
    (comp (ref "C280")
      (value "0.1")
      (footprint "C0402-Phillips")
      (description "Конденсатор")
      (fields (field (name "MANUFACTURER") "MURATA") (field (name "TOLERANCE") "20%"))
      (libsource (lib "Capacitors") (part "C0402"))
    )
    (comp (ref "C281")
      (value "0.1")
      (footprint "C0402-Phillips")
      (description "Конденсатор")
      (fields (field (name "MANUFACTURER") "MURATA") (field (name "TOLERANCE") "20%"))
      (libsource (lib "Capacitors") (part "C0402"))
    )
    (comp (ref "C282")
      (value "0.1")
      (footprint "C0402-Phillips")
      (description "Конденсатор")
      (fields (field (name "MANUFACTURER") "MURATA") (field (name "TOLERANCE") "20%"))
      (libsource (lib "Capacitors") (part "C0402"))
    )
    (comp (ref "C283")
      (value "33uF CER")
      (footprint "C0805-Phillips")
      (description "Конденсатор")
      (fields (field (name "MANUFACTURER") "MURATA") (field (name "TOLERANCE") "20%"))
      (libsource (lib "altium-import") (part "root_1_C0805_"))
    )
    (comp (ref "C284")
      (value "33uF CER")
      (footprint "C0805-Phillips")
      (description "Конденсатор")
      (fields (field (name "MANUFACTURER") "MURATA") (field (name "TOLERANCE") "20%"))
      (libsource (lib "altium-import") (part "root_1_C0805_"))
    )
    (comp (ref "C285")
      (value "33uF CER")
      (footprint "C0805-Phillips")
      (description "Конденсатор")
      (fields (field (name "MANUFACTURER") "MURATA") (field (name "TOLERANCE") "20%"))
      (libsource (lib "altium-import") (part "root_1_C0805_"))
    )
    (comp (ref "C286")
      (value "2.2")
      (footprint "C0402-Phillips")
      (description "Конденсатор")
      (fields (field (name "MANUFACTURER") "MURATA") (field (name "TOLERANCE") "20%"))
      (libsource (lib "Capacitors") (part "C0402"))
    )
    (comp (ref "C287")
      (value "2.2")
      (footprint "C0402-Phillips")
      (description "Конденсатор")
      (fields (field (name "MANUFACTURER") "MURATA") (field (name "TOLERANCE") "20%"))
      (libsource (lib "Capacitors") (part "C0402"))
    )
    (comp (ref "D1")
      (value "STPS3L60U")
      (footprint "SMB")
      (description "Диод Шоттки")
      (fields (field (name "MANUFACTURER") "ST"))
      (libsource (lib "Diods") (part "B3x0B"))
    )
    (comp (ref "D2")
      (value "STPS3L60U")
      (footprint "SMB")
      (description "Диод Шоттки")
      (fields (field (name "MANUFACTURER") "ST"))
      (libsource (lib "Diods") (part "B3x0B"))
    )
    (comp (ref "D3")
      (value "STPS3L60U")
      (footprint "SMB")
      (description "Диод Шоттки")
      (fields (field (name "MANUFACTURER") "ST"))
      (libsource (lib "Diods") (part "B3x0B"))
    )
    (comp (ref "D4")
      (value "LNBTVS4-304S")
      (footprint "SMC")
      (description "Диод")
      (fields (field (name "MANUFACTURER") "ST"))
      (libsource (lib "altium-import") (part "root_0_STPS3L40S_"))
    )
    (comp (ref "F1")
      (value "1.85A")
      (footprint "Andy:FUSE2920")
      (description "FUSE PTC resetable")
      (fields (field (name "MANUFACTURER") "Bel Fuse"))
      (libsource (lib "Andy") (part "FUSE_PTC"))
    )
    (comp (ref "L35")
      (value "15 uH")
      (footprint "SRN8040")
      (description "Индуктивность")
      (fields (field (name "MANUFACTURER") "BOURNS") (field (name "NAME") "SRN8040"))
      (libsource (lib "Andy") (part "L-SRN8040"))
    )
    (comp (ref "L36")
      (value "15 uH")
      (footprint "SRN8040")
      (description "Индуктивность")
      (fields (field (name "MANUFACTURER") "BOURNS") (field (name "NAME") "SRN8040"))
      (libsource (lib "Andy") (part "L-SRN8040"))
    )
    (comp (ref "L37")
      (value "15 uH")
      (footprint "SRN8040")
      (description "Индуктивность")
      (fields (field (name "MANUFACTURER") "BOURNS") (field (name "NAME") "SRN8040"))
      (libsource (lib "Andy") (part "L-SRN8040"))
    )
    (comp (ref "L40")
      (value "TI201209-121")
      (footprint "TI2012-Phillips")
      (description "Дроссель ЭМС")
      (fields (field (name "MANUFACTURER") "MURATA"))
      (libsource (lib "Andy") (part "TI2012_1"))
    )
    (comp (ref "L41")
      (value "TI201209-121")
      (footprint "TI2012-Phillips")
      (description "Дроссель ЭМС")
      (fields (field (name "MANUFACTURER") "MURATA"))
      (libsource (lib "Andy") (part "TI2012_1"))
    )
    (comp (ref "L42")
      (value "TI201209-121")
      (footprint "TI2012-Phillips")
      (description "Дроссель ЭМС")
      (fields (field (name "MANUFACTURER") "MURATA"))
      (libsource (lib "Andy") (part "TI2012_1"))
    )
    (comp (ref "L43")
      (value "TI201209-121")
      (footprint "TI2012-Phillips")
      (description "Дроссель ЭМС")
      (fields (field (name "MANUFACTURER") "MURATA"))
      (libsource (lib "Andy") (part "TI2012_1"))
    )
    (comp (ref "L44")
      (value "TI201209-121")
      (footprint "TI2012-Phillips")
      (description "Дроссель ЭМС")
      (fields (field (name "MANUFACTURER") "MURATA"))
      (libsource (lib "Andy") (part "TI2012_1"))
    )
    (comp (ref "L45")
      (value "TI160808U601")
      (footprint "Ti160808-Phillips")
      (description "Дроссель ЭМС")
      (fields (field (name "MANUFACTURER") "MURATA"))
      (libsource (lib "altium-import") (part "root_3_TI160808_"))
    )
    (comp (ref "Q3")
      (value "BCP69")
      (footprint "SOT-223")
      (description "Транзистор")
      (fields (field (name "MANUFACTURER") "INFINEON"))
      (libsource (lib "altium-import") (part "root_0_mirrored_BCP69_"))
    )
    (comp (ref "Q4")
      (value "BC817-40")
      (footprint "SOT23-Philips")
      (description "Транзистор")
      (fields (field (name "MANUFACTURER") "Philips"))
      (libsource (lib "Transistors") (part "BC 817"))
    )
    (comp (ref "R128")
      (value "3k3")
      (footprint "R0603-PHILLIPS")
      (description "Резистор")
      (fields (field (name "MANUFACTURER") "YAGEO") (field (name "TOLERANCE") "5%"))
      (libsource (lib "altium-import") (part "root_1_R0603_"))
    )
    (comp (ref "R129")
      (value "4k7")
      (footprint "R0603-PHILLIPS")
      (description "Резистор")
      (fields (field (name "MANUFACTURER") "YAGEO") (field (name "TOLERANCE") "5%"))
      (libsource (lib "altium-import") (part "root_1_R0603_"))
    )
    (comp (ref "R131")
      (value "4k7")
      (footprint "R0603-PHILLIPS")
      (description "Резистор")
      (fields (field (name "MANUFACTURER") "YAGEO") (field (name "TOLERANCE") "5%"))
      (libsource (lib "altium-import") (part "root_0_R0603_"))
    )
    (comp (ref "R132")
      (value "4k7")
      (footprint "R0603-PHILLIPS")
      (description "Резистор")
      (fields (field (name "MANUFACTURER") "YAGEO") (field (name "TOLERANCE") "5%"))
      (libsource (lib "altium-import") (part "root_0_R0603_"))
    )
    (comp (ref "R133")
      (value "0")
      (footprint "R0603-PHILLIPS")
      (description "Резистор")
      (fields (field (name "MANUFACTURER") "YAGEO") (field (name "TOLERANCE") "5%"))
      (libsource (lib "altium-import") (part "root_2_R0603_"))
    )
    (comp (ref "R136")
      (value "5k6")
      (footprint "R0603-PHILLIPS")
      (description "Резистор")
      (fields (field (name "MANUFACTURER") "YAGEO") (field (name "TOLERANCE") "5%"))
      (libsource (lib "altium-import") (part "root_0_R0603_"))
    )
    (comp (ref "R137")
      (value "5k1")
      (footprint "R0603-PHILLIPS")
      (description "Резистор")
      (fields (field (name "MANUFACTURER") "YAGEO") (field (name "TOLERANCE") "5%"))
      (libsource (lib "altium-import") (part "root_0_R0603_"))
    )
    (comp (ref "R138")
      (value "120")
      (footprint "R0603-PHILLIPS")
      (description "Резистор")
      (fields (field (name "MANUFACTURER") "YAGEO") (field (name "TOLERANCE") "5%"))
      (libsource (lib "altium-import") (part "root_0_R0603_"))
    )
    (comp (ref "R168")
      (value "1k2")
      (footprint "R0603-PHILLIPS")
      (description "Резистор")
      (fields (field (name "MANUFACTURER") "YAGEO") (field (name "TOLERANCE") "5%"))
      (libsource (lib "altium-import") (part "root_1_R0603_"))
    )
    (comp (ref "R169")
      (value "4k7")
      (footprint "R0603-PHILLIPS")
      (description "Резистор")
      (fields (field (name "MANUFACTURER") "YAGEO") (field (name "TOLERANCE") "5%"))
      (libsource (lib "altium-import") (part "root_0_R0603_"))
    )
    (comp (ref "R170")
      (value "4k7")
      (footprint "R0603-PHILLIPS")
      (description "Резистор")
      (fields (field (name "MANUFACTURER") "YAGEO") (field (name "TOLERANCE") "5%"))
      (libsource (lib "altium-import") (part "root_0_R0603_"))
    )
    (comp (ref "R171")
      (value "0")
      (footprint "R0603-PHILLIPS")
      (description "Резистор")
      (fields (field (name "MANUFACTURER") "YAGEO") (field (name "TOLERANCE") "5%"))
      (libsource (lib "altium-import") (part "root_0_R0603_"))
    )
    (comp (ref "R172")
      (value "??")
      (footprint "R0603-PHILLIPS")
      (description "Резистор")
      (fields (field (name "MANUFACTURER") "YAGEO") (field (name "TOLERANCE") "5%"))
      (libsource (lib "altium-import") (part "root_0_R0603_"))
    )
    (comp (ref "R173")
      (value "10k")
      (footprint "R0603-PHILLIPS")
      (description "Резистор")
      (fields (field (name "MANUFACTURER") "YAGEO") (field (name "TOLERANCE") "5%"))
      (libsource (lib "altium-import") (part "root_0_R0603_"))
    )
    (comp (ref "R174")
      (value "10k")
      (footprint "R0603-PHILLIPS")
      (description "Резистор")
      (fields (field (name "MANUFACTURER") "YAGEO") (field (name "TOLERANCE") "5%"))
      (libsource (lib "altium-import") (part "root_0_R0603_"))
    )
    (comp (ref "U8")
      (value "XC6SLX75-2FGG484C")
      (footprint "FBGA484")
      (fields (field (name "MANUFACTURER") "Xilinx"))
      (libsource (lib "MicroCircuitsM-Z") (part "XC6SLX75-2FGG484C"))
    )
    (comp (ref "U9")
      (value "ET1011C2-CI-DT")
      (footprint "QFN-84(10x10/0/4mm)with_pad")
      (description "Микросхема")
      (fields (field (name "MANUFACTURER") "LSI"))
      (libsource (lib "altium-import") (part "root_0_ET1011C2-CI-DT_"))
    )
    (comp (ref "U11")
      (value "CY7C1354C-166AXI")
      (footprint "QFP-10020X14/0.65]")
      (description "Микросхема")
      (fields (field (name "MANUFACTURER") "Cypress"))
      (libsource (lib "MicroCircuits0-L") (part "CY7C1354C-166AXI"))
    )
    (comp (ref "U15")
      (value "L5973AD")
      (footprint "SOIC8 - BackGND - 0.4mm dia")
      (description "Микросхема")
      (fields (field (name "MANUFACTURER") "ST"))
      (libsource (lib "altium-import") (part "root_0_mirrored_L5973D_"))
    )
    (comp (ref "U16")
      (value "L5973AD")
      (footprint "SOIC8 - BackGND - 0.4mm dia")
      (description "Микросхема")
      (fields (field (name "MANUFACTURER") "ST"))
      (libsource (lib "altium-import") (part "root_0_mirrored_L5973D_"))
    )
    (comp (ref "U17")
      (value "LD1117S")
      (footprint "Foot3-4pins:SOT-223-1")
      (description "Микросхема")
      (fields (field (name "MANUFACTURER") "STMicro"))
      (libsource (lib "altium-import") (part "root_0_LD1117ADJ_"))
    )
    (comp (ref "U34")
      (value "L5973AD")
      (footprint "SOIC8 - BackGND - 0.4mm dia")
      (description "Микросхема")
      (fields (field (name "MANUFACTURER") "ST"))
      (libsource (lib "altium-import") (part "root_0_mirrored_L5973D_"))
    )
    (comp (ref "U35")
      (value "MAX6665ASA")
      (footprint "SO-8")
      (description "Микросхема")
      (fields (field (name "MANUFACTURER") "Maxim"))
      (libsource (lib "MicroCircuitsM-Z") (part "MAX6665ASA"))
    )
    (comp (ref "X5")
      (value "MF-2MRA")
      (footprint "MF-2MRA")
      (description "Разъем")
      (fields (field (name "MANUFACTURER") "BM"))
      (libsource (lib "altium-import") (part "root_0_mirrored_MF-2MRA_"))
    )
    (comp (ref "X17")
      (value "FAN1")
      (footprint "Andy:WF-2")
      (description "Разъем")
      (fields (field (name "MANUFACTURER") "BM"))
      (libsource (lib "Andy") (part "WF-2"))
    )
    (comp (ref "X18")
      (value "FAN2")
      (footprint "Andy:WF-2")
      (description "Разъем")
      (fields (field (name "MANUFACTURER") "BM"))
      (libsource (lib "Andy") (part "WF-2"))
    )
  )
  (nets
    (net (code "1") (name "+1,2VFPGA") (class "Default")
      (node (ref "C138") (pin "1") (pinfunction "+_1") (pintype "passive"))
      (node (ref "C148") (pin "1") (pinfunction "1_1") (pintype "passive"))
      (node (ref "C154") (pin "1") (pinfunction "1_1") (pintype "passive"))
      (node (ref "C260") (pin "1") (pinfunction "1_1") (pintype "passive"))
      (node (ref "C262") (pin "1") (pinfunction "1_1") (pintype "passive"))
      (node (ref "C263") (pin "1") (pinfunction "1_1") (pintype "passive"))
      (node (ref "C264") (pin "1") (pinfunction "1_1") (pintype "passive"))
      (node (ref "C265") (pin "1") (pinfunction "1_1") (pintype "passive"))
      (node (ref "C268") (pin "1") (pinfunction "1_1") (pintype "passive"))
      (node (ref "C270") (pin "1") (pinfunction "1_1") (pintype "passive"))
      (node (ref "C271") (pin "1") (pinfunction "1_1") (pintype "passive"))
      (node (ref "C272") (pin "1") (pinfunction "1_1") (pintype "passive"))
      (node (ref "C273") (pin "1") (pinfunction "1_1") (pintype "passive"))
      (node (ref "C274") (pin "1") (pinfunction "1_1") (pintype "passive"))
      (node (ref "C276") (pin "1") (pinfunction "1_1") (pintype "passive"))
      (node (ref "C277") (pin "1") (pinfunction "1_1") (pintype "passive"))
      (node (ref "R138") (pin "1") (pinfunction "1_1") (pintype "passive"))
      (node (ref "U17") (pin "2") (pinfunction "Vout_2") (pintype "passive"))
      (node (ref "U8") (pin "J10") (pinfunction "VCCINT_J10") (pintype "power_in"))
      (node (ref "U8") (pin "J12") (pinfunction "VCCINT_J12") (pintype "power_in"))
      (node (ref "U8") (pin "J14") (pinfunction "VCCINT_J14") (pintype "power_in"))
      (node (ref "U8") (pin "J8") (pinfunction "VCCINT_J8") (pintype "power_in"))
      (node (ref "U8") (pin "K11") (pinfunction "VCCINT_K11") (pintype "power_in"))
      (node (ref "U8") (pin "K13") (pinfunction "VCCINT_K13") (pintype "power_in"))
      (node (ref "U8") (pin "K9") (pinfunction "VCCINT_K9") (pintype "power_in"))
      (node (ref "U8") (pin "L10") (pinfunction "VCCINT_L10") (pintype "power_in"))
      (node (ref "U8") (pin "L12") (pinfunction "VCCINT_L12") (pintype "power_in"))
      (node (ref "U8") (pin "L14") (pinfunction "VCCINT_L14") (pintype "power_in"))
      (node (ref "U8") (pin "M11") (pinfunction "VCCINT_M11") (pintype "power_in"))
      (node (ref "U8") (pin "M13") (pinfunction "VCCINT_M13") (pintype "power_in"))
      (node (ref "U8") (pin "M9") (pinfunction "VCCINT_M9") (pintype "power_in"))
      (node (ref "U8") (pin "N10") (pinfunction "VCCINT_N10") (pintype "power_in"))
      (node (ref "U8") (pin "N12") (pinfunction "VCCINT_N12") (pintype "power_in"))
      (node (ref "U8") (pin "N14") (pinfunction "VCCINT_N14") (pintype "power_in"))
      (node (ref "U8") (pin "P11") (pinfunction "VCCINT_P11") (pintype "power_in"))
      (node (ref "U8") (pin "P13") (pinfunction "VCCINT_P13") (pintype "power_in"))
      (node (ref "U8") (pin "P9") (pinfunction "VCCINT_P9") (pintype "power_in"))
      (node (ref "U8") (pin "R14") (pinfunction "VCCINT_R14") (pintype "power_in"))
    )
    (net (code "2") (name "+2,5VETH") (class "Default")
      (node (ref "C157") (pin "1") (pinfunction "1_1") (pintype "passive"))
      (node (ref "C163") (pin "1") (pinfunction "1_1") (pintype "passive"))
      (node (ref "C167") (pin "1") (pinfunction "+_1") (pintype "passive"))
      (node (ref "C171") (pin "1") (pinfunction "+_1") (pintype "passive"))
      (node (ref "C228") (pin "2") (pinfunction "2_2") (pintype "passive"))
      (node (ref "C229") (pin "1") (pinfunction "1_1") (pintype "passive"))
      (node (ref "C230") (pin "1") (pinfunction "1_1") (pintype "passive"))
      (node (ref "C231") (pin "1") (pinfunction "1_1") (pintype "passive"))
      (node (ref "C232") (pin "1") (pinfunction "1_1") (pintype "passive"))
      (node (ref "C233") (pin "1") (pinfunction "1_1") (pintype "passive"))
      (node (ref "C234") (pin "1") (pinfunction "1_1") (pintype "passive"))
      (node (ref "C235") (pin "1") (pinfunction "1_1") (pintype "passive"))
      (node (ref "L42") (pin "2") (pinfunction "2_2") (pintype "passive"))
      (node (ref "L45") (pin "1") (pinfunction "1_1") (pintype "passive"))
      (node (ref "Q3") (pin "3") (pinfunction "E_3") (pintype "passive"))
      (node (ref "U9") (pin "4") (pinfunction "DVDD_IO_4") (pintype "power_in"))
      (node (ref "U9") (pin "45") (pinfunction "VDD_REG_45") (pintype "passive"))
      (node (ref "U9") (pin "52") (pinfunction "DVDD_IO_52") (pintype "power_in"))
      (node (ref "U9") (pin "58") (pinfunction "DVDD_IO_58") (pintype "power_in"))
      (node (ref "U9") (pin "64") (pinfunction "DVDD_IO_64") (pintype "power_in"))
      (node (ref "U9") (pin "71") (pinfunction "DVDD_IO_71") (pintype "power_in"))
      (node (ref "U9") (pin "76") (pinfunction "DVDD_IO_76") (pintype "power_in"))
    )
    (net (code "3") (name "+2,5VFPGA") (class "Default")
      (node (ref "C156") (pin "1") (pinfunction "1_1") (pintype "passive"))
      (node (ref "C162") (pin "1") (pinfunction "1_1") (pintype "passive"))
      (node (ref "C166") (pin "1") (pinfunction "+_1") (pintype "passive"))
      (node (ref "C172") (pin "2") (pinfunction "2_2") (pintype "passive"))
      (node (ref "C175") (pin "2") (pinfunction "2_2") (pintype "passive"))
      (node (ref "C176") (pin "2") (pinfunction "2_2") (pintype "passive"))
      (node (ref "C177") (pin "2") (pinfunction "2_2") (pintype "passive"))
      (node (ref "C178") (pin "2") (pinfunction "2_2") (pintype "passive"))
      (node (ref "C179") (pin "2") (pinfunction "2_2") (pintype "passive"))
      (node (ref "C180") (pin "2") (pinfunction "2_2") (pintype "passive"))
      (node (ref "C181") (pin "2") (pinfunction "2_2") (pintype "passive"))
      (node (ref "C182") (pin "2") (pinfunction "2_2") (pintype "passive"))
      (node (ref "C183") (pin "2") (pinfunction "2_2") (pintype "passive"))
      (node (ref "C184") (pin "2") (pinfunction "2_2") (pintype "passive"))
      (node (ref "C185") (pin "2") (pinfunction "2_2") (pintype "passive"))
      (node (ref "C186") (pin "2") (pinfunction "2_2") (pintype "passive"))
      (node (ref "C187") (pin "2") (pinfunction "2_2") (pintype "passive"))
      (node (ref "C188") (pin "2") (pinfunction "2_2") (pintype "passive"))
      (node (ref "C189") (pin "2") (pinfunction "2_2") (pintype "passive"))
      (node (ref "C190") (pin "2") (pinfunction "2_2") (pintype "passive"))
      (node (ref "C191") (pin "2") (pinfunction "2_2") (pintype "passive"))
      (node (ref "C192") (pin "2") (pinfunction "2_2") (pintype "passive"))
      (node (ref "C193") (pin "2") (pinfunction "2_2") (pintype "passive"))
      (node (ref "C204") (pin "2") (pinfunction "2_2") (pintype "passive"))
      (node (ref "C205") (pin "2") (pinfunction "2_2") (pintype "passive"))
      (node (ref "C206") (pin "2") (pinfunction "2_2") (pintype "passive"))
      (node (ref "C207") (pin "2") (pinfunction "2_2") (pintype "passive"))
      (node (ref "C208") (pin "2") (pinfunction "2_2") (pintype "passive"))
      (node (ref "C209") (pin "2") (pinfunction "2_2") (pintype "passive"))
      (node (ref "C210") (pin "2") (pinfunction "2_2") (pintype "passive"))
      (node (ref "C211") (pin "2") (pinfunction "2_2") (pintype "passive"))
      (node (ref "C212") (pin "2") (pinfunction "2_2") (pintype "passive"))
      (node (ref "C213") (pin "2") (pinfunction "2_2") (pintype "passive"))
      (node (ref "L41") (pin "2") (pinfunction "2_2") (pintype "passive"))
      (node (ref "U8") (pin "B11") (pinfunction "VCCO_0_B11") (pintype "power_in"))
      (node (ref "U8") (pin "B15") (pinfunction "VCCO_0_B15") (pintype "power_in"))
      (node (ref "U8") (pin "B19") (pinfunction "VCCO_0_B19") (pintype "power_in"))
      (node (ref "U8") (pin "B4") (pinfunction "VCCO_0_B4") (pintype "power_in"))
      (node (ref "U8") (pin "B7") (pinfunction "VCCO_0_B7") (pintype "power_in"))
      (node (ref "U8") (pin "C2") (pinfunction "VCCO_3_C2") (pintype "power_in"))
      (node (ref "U8") (pin "C21") (pinfunction "VCCO_1_C21") (pintype "power_in"))
      (node (ref "U8") (pin "E13") (pinfunction "VCCO_0_E13") (pintype "power_in"))
      (node (ref "U8") (pin "E17") (pinfunction "VCCO_0_E17") (pintype "power_in"))
      (node (ref "U8") (pin "E19") (pinfunction "VCCO_1_E19") (pintype "power_in"))
      (node (ref "U8") (pin "E9") (pinfunction "VCCO_0_E9") (pintype "power_in"))
      (node (ref "U8") (pin "F4") (pinfunction "VCCO_3_F4") (pintype "power_in"))
      (node (ref "U8") (pin "F6") (pinfunction "VCCO_3_F6") (pintype "power_in"))
      (node (ref "U8") (pin "G10") (pinfunction "VCCO_0_G10") (pintype "power_in"))
      (node (ref "U8") (pin "G14") (pinfunction "VCCO_0_G14") (pintype "power_in"))
      (node (ref "U8") (pin "G2") (pinfunction "VCCO_3_G2") (pintype "power_in"))
      (node (ref "U8") (pin "G21") (pinfunction "VCCO_1_G21") (pintype "power_in"))
      (node (ref "U8") (pin "J18") (pinfunction "VCCO_1_J18") (pintype "power_in"))
      (node (ref "U8") (pin "J5") (pinfunction "VCCO_3_J5") (pintype "power_in"))
      (node (ref "U8") (pin "L16") (pinfunction "VCCO_1_L16") (pintype "power_in"))
      (node (ref "U8") (pin "L2") (pinfunction "VCCO_3_L2") (pintype "power_in"))
      (node (ref "U8") (pin "L21") (pinfunction "VCCO_1_L21") (pintype "power_in"))
      (node (ref "U8") (pin "L7") (pinfunction "VCCO_3_L7") (pintype "power_in"))
      (node (ref "U8") (pin "N18") (pinfunction "VCCO_1_N18") (pintype "power_in"))
      (node (ref "U8") (pin "N5") (pinfunction "VCCO_3_N5") (pintype "power_in"))
      (node (ref "U8") (pin "R2") (pinfunction "VCCO_3_R2") (pintype "power_in"))
      (node (ref "U8") (pin "R21") (pinfunction "VCCO_1_R21") (pintype "power_in"))
      (node (ref "U8") (pin "U18") (pinfunction "VCCO_1_U18") (pintype "power_in"))
      (node (ref "U8") (pin "U5") (pinfunction "VCCO_3_U5") (pintype "power_in"))
      (node (ref "U8") (pin "W2") (pinfunction "VCCO_3_W2") (pintype "power_in"))
      (node (ref "U8") (pin "W21") (pinfunction "VCCO_1_W21") (pintype "power_in"))
    )
    (net (code "4") (name "+2,5VRAM") (class "Default")
      (node (ref "C158") (pin "1") (pinfunction "1_1") (pintype "passive"))
      (node (ref "C164") (pin "1") (pinfunction "1_1") (pintype "passive"))
      (node (ref "C168") (pin "1") (pinfunction "+_1") (pintype "passive"))
      (node (ref "C215") (pin "2") (pinfunction "2_2") (pintype "passive"))
      (node (ref "C216") (pin "2") (pinfunction "2_2") (pintype "passive"))
      (node (ref "C217") (pin "2") (pinfunction "2_2") (pintype "passive"))
      (node (ref "C218") (pin "2") (pinfunction "2_2") (pintype "passive"))
      (node (ref "C219") (pin "2") (pinfunction "2_2") (pintype "passive"))
      (node (ref "C220") (pin "2") (pinfunction "2_2") (pintype "passive"))
      (node (ref "C221") (pin "2") (pinfunction "2_2") (pintype "passive"))
      (node (ref "C222") (pin "2") (pinfunction "2_2") (pintype "passive"))
      (node (ref "L43") (pin "2") (pinfunction "2_2") (pintype "passive"))
      (node (ref "U11") (pin "11") (pinfunction "VDDQ_11") (pintype "passive"))
      (node (ref "U11") (pin "20") (pinfunction "VDDQ_20") (pintype "passive"))
      (node (ref "U11") (pin "27") (pinfunction "VDDQ_27") (pintype "passive"))
      (node (ref "U11") (pin "4") (pinfunction "VDDQ_4") (pintype "passive"))
      (node (ref "U11") (pin "54") (pinfunction "VDDQ_54") (pintype "passive"))
      (node (ref "U11") (pin "61") (pinfunction "VDDQ_61") (pintype "passive"))
      (node (ref "U11") (pin "70") (pinfunction "VDDQ_70") (pintype "passive"))
      (node (ref "U11") (pin "77") (pinfunction "VDDQ_77") (pintype "passive"))
    )
    (net (code "5") (name "+3,3V1") (class "Default")
      (node (ref "C136") (pin "1") (pinfunction "1_1") (pintype "passive"))
      (node (ref "C141") (pin "1") (pinfunction "+_1") (pintype "passive"))
      (node (ref "C147") (pin "1") (pinfunction "1_1") (pintype "passive"))
      (node (ref "C150") (pin "1") (pinfunction "1_1") (pintype "passive"))
      (node (ref "C279") (pin "1") (pinfunction "1_1") (pintype "passive"))
      (node (ref "L36") (pin "2") (pinfunction "2_2") (pintype "passive"))
      (node (ref "L40") (pin "1") (pinfunction "1_1") (pintype "passive"))
      (node (ref "R136") (pin "1") (pinfunction "1_1") (pintype "passive"))
      (node (ref "R173") (pin "1") (pinfunction "1_1") (pintype "passive"))
      (node (ref "R174") (pin "1") (pinfunction "1_1") (pintype "passive"))
      (node (ref "U35") (pin "2") (pinfunction "~{F_ON}_2") (pintype "passive"))
      (node (ref "U35") (pin "7") (pinfunction "VDD_7") (pintype "passive"))
    )
    (net (code "6") (name "+3,3VFPGA") (class "Default")
      (node (ref "C159") (pin "1") (pinfunction "1_1") (pintype "passive"))
      (node (ref "C161") (pin "1") (pinfunction "1_1") (pintype "passive"))
      (node (ref "C165") (pin "1") (pinfunction "+_1") (pintype "passive"))
      (node (ref "C174") (pin "2") (pinfunction "2_2") (pintype "passive"))
      (node (ref "C194") (pin "2") (pinfunction "2_2") (pintype "passive"))
      (node (ref "C196") (pin "2") (pinfunction "2_2") (pintype "passive"))
      (node (ref "C197") (pin "2") (pinfunction "2_2") (pintype "passive"))
      (node (ref "C198") (pin "2") (pinfunction "2_2") (pintype "passive"))
      (node (ref "C199") (pin "2") (pinfunction "2_2") (pintype "passive"))
      (node (ref "C200") (pin "2") (pinfunction "2_2") (pintype "passive"))
      (node (ref "C201") (pin "2") (pinfunction "2_2") (pintype "passive"))
      (node (ref "C202") (pin "2") (pinfunction "2_2") (pintype "passive"))
      (node (ref "C203") (pin "2") (pinfunction "2_2") (pintype "passive"))
      (node (ref "C223") (pin "2") (pinfunction "2_2") (pintype "passive"))
      (node (ref "C224") (pin "2") (pinfunction "2_2") (pintype "passive"))
      (node (ref "C225") (pin "2") (pinfunction "2_2") (pintype "passive"))
      (node (ref "C227") (pin "2") (pinfunction "2_2") (pintype "passive"))
      (node (ref "C246") (pin "1") (pinfunction "1_1") (pintype "passive"))
      (node (ref "C247") (pin "1") (pinfunction "1_1") (pintype "passive"))
      (node (ref "C248") (pin "1") (pinfunction "1_1") (pintype "passive"))
      (node (ref "C249") (pin "1") (pinfunction "1_1") (pintype "passive"))
      (node (ref "C250") (pin "1") (pinfunction "1_1") (pintype "passive"))
      (node (ref "C251") (pin "1") (pinfunction "1_1") (pintype "passive"))
      (node (ref "C252") (pin "1") (pinfunction "1_1") (pintype "passive"))
      (node (ref "C254") (pin "1") (pinfunction "1_1") (pintype "passive"))
      (node (ref "C255") (pin "1") (pinfunction "1_1") (pintype "passive"))
      (node (ref "C256") (pin "1") (pinfunction "1_1") (pintype "passive"))
      (node (ref "C257") (pin "1") (pinfunction "1_1") (pintype "passive"))
      (node (ref "C258") (pin "1") (pinfunction "1_1") (pintype "passive"))
      (node (ref "C259") (pin "1") (pinfunction "1_1") (pintype "passive"))
      (node (ref "L40") (pin "2") (pinfunction "2_2") (pintype "passive"))
      (node (ref "U11") (pin "15") (pinfunction "VDD_15") (pintype "passive"))
      (node (ref "U11") (pin "41") (pinfunction "VDD_41") (pintype "passive"))
      (node (ref "U11") (pin "65") (pinfunction "VDD_65") (pintype "passive"))
      (node (ref "U11") (pin "91") (pinfunction "VDD_91") (pintype "passive"))
      (node (ref "U8") (pin "AA11") (pinfunction "VCCO_2_AA11") (pintype "power_in"))
      (node (ref "U8") (pin "AA15") (pinfunction "VCCO_2_AA15") (pintype "power_in"))
      (node (ref "U8") (pin "AA19") (pinfunction "VCCO_2_AA19") (pintype "power_in"))
      (node (ref "U8") (pin "AA3") (pinfunction "VCCO_2_AA3") (pintype "power_in"))
      (node (ref "U8") (pin "AA7") (pinfunction "VCCO_2_AA7") (pintype "power_in"))
      (node (ref "U8") (pin "D16") (pinfunction "VCCAUX_D16") (pintype "power_in"))
      (node (ref "U8") (pin "F11") (pinfunction "VCCAUX_F11") (pintype "power_in"))
      (node (ref "U8") (pin "G12") (pinfunction "VCCAUX_G12") (pintype "power_in"))
      (node (ref "U8") (pin "H15") (pinfunction "VCCAUX_H15") (pintype "power_in"))
      (node (ref "U8") (pin "H9") (pinfunction "VCCAUX_H9") (pintype "power_in"))
      (node (ref "U8") (pin "K15") (pinfunction "VCCAUX_K15") (pintype "power_in"))
      (node (ref "U8") (pin "L8") (pinfunction "VCCAUX_L8") (pintype "power_in"))
      (node (ref "U8") (pin "M15") (pinfunction "VCCAUX_M15") (pintype "power_in"))
      (node (ref "U8") (pin "N8") (pinfunction "VCCAUX_N8") (pintype "power_in"))
      (node (ref "U8") (pin "R10") (pinfunction "VCCAUX_R10") (pintype "power_in"))
      (node (ref "U8") (pin "R12") (pinfunction "VCCAUX_R12") (pintype "power_in"))
      (node (ref "U8") (pin "R17") (pinfunction "VBATT_R17") (pintype "power_in"))
      (node (ref "U8") (pin "R6") (pinfunction "VCCAUX_R6") (pintype "power_in"))
      (node (ref "U8") (pin "T13") (pinfunction "VCCO_2_T13") (pintype "power_in"))
      (node (ref "U8") (pin "T9") (pinfunction "VCCO_2_T9") (pintype "power_in"))
      (node (ref "U8") (pin "U11") (pinfunction "VCCAUX_U11") (pintype "power_in"))
      (node (ref "U8") (pin "V12") (pinfunction "VCCO_2_V12") (pintype "power_in"))
      (node (ref "U8") (pin "V16") (pinfunction "VCCO_2_V16") (pintype "power_in"))
      (node (ref "U8") (pin "V6") (pinfunction "VCCAUX_V6") (pintype "power_in"))
      (node (ref "U8") (pin "V8") (pinfunction "VCCO_2_V8") (pintype "power_in"))
      (node (ref "U8") (pin "W5") (pinfunction "VCCO_2_W5") (pintype "power_in"))
    )
    (net (code "7") (name "+6V") (class "Default")
      (node (ref "C125") (pin "1") (pinfunction "+_1") (pintype "passive"))
      (node (ref "L44") (pin "2") (pinfunction "2_2") (pintype "passive"))
    )
    (net (code "8") (name "+6V1") (class "Default")
      (node (ref "C113") (pin "1") (pinfunction "1_1") (pintype "passive"))
      (node (ref "C131") (pin "1") (pinfunction "+_1") (pintype "passive"))
      (node (ref "C261") (pin "1") (pinfunction "1_1") (pintype "passive"))
      (node (ref "C269") (pin "1") (pinfunction "1_1") (pintype "passive"))
      (node (ref "L35") (pin "2") (pinfunction "2_2") (pintype "passive"))
      (node (ref "L44") (pin "1") (pinfunction "1_1") (pintype "passive"))
      (node (ref "R170") (pin "1") (pinfunction "1_1") (pintype "passive"))
      (node (ref "R172") (pin "1") (pinfunction "1_1") (pintype "passive"))
    )
    (net (code "9") (name "+12V") (class "Default")
      (node (ref "C114") (pin "1") (pinfunction "1_1") (pintype "passive"))
      (node (ref "C115") (pin "1") (pinfunction "1_1") (pintype "passive"))
      (node (ref "C116") (pin "1") (pinfunction "1_1") (pintype "passive"))
      (node (ref "C117") (pin "1") (pinfunction "1_1") (pintype "passive"))
      (node (ref "C118") (pin "1") (pinfunction "1_1") (pintype "passive"))
      (node (ref "C119") (pin "1") (pinfunction "1_1") (pintype "passive"))
      (node (ref "D4") (pin "2") (pinfunction "C_2") (pintype "passive"))
      (node (ref "F1") (pin "2") (pinfunction "2_2") (pintype "passive"))
      (node (ref "R171") (pin "1") (pinfunction "1_1") (pintype "passive"))
      (node (ref "U15") (pin "8") (pinfunction "Vcc_8") (pintype "passive"))
      (node (ref "U16") (pin "8") (pinfunction "Vcc_8") (pintype "passive"))
      (node (ref "U34") (pin "8") (pinfunction "Vcc_8") (pintype "passive"))
      (node (ref "X18") (pin "1") (pinfunction "1_1") (pintype "passive"))
    )
    (net (code "10") (name "/FAN_ON") (class "Default")
      (node (ref "U35") (pin "4") (pinfunction "FanOn_4") (pintype "passive"))
    )
    (net (code "11") (name "/INHIBIT") (class "Default")
      (node (ref "Q4") (pin "3") (pinfunction "C_3") (pintype "passive"))
      (node (ref "U16") (pin "3") (pinfunction "INH_3") (pintype "passive"))
      (node (ref "U34") (pin "3") (pinfunction "INH_3") (pintype "passive"))
    )
    (net (code "12") (name "/OVERHEAT") (class "Default")
      (node (ref "R173") (pin "2") (pinfunction "2_2") (pintype "passive"))
      (node (ref "U35") (pin "6") (pinfunction "~{WRN}_6") (pintype "passive"))
    )
    (net (code "13") (name "GND") (class "Default")
      (node (ref "C113") (pin "2") (pinfunction "2_2") (pintype "passive"))
      (node (ref "C114") (pin "2") (pinfunction "2_2") (pintype "passive"))
      (node (ref "C115") (pin "2") (pinfunction "2_2") (pintype "passive"))
      (node (ref "C116") (pin "2") (pinfunction "2_2") (pintype "passive"))
      (node (ref "C117") (pin "2") (pinfunction "2_2") (pintype "passive"))
      (node (ref "C118") (pin "2") (pinfunction "2_2") (pintype "passive"))
      (node (ref "C119") (pin "2") (pinfunction "2_2") (pintype "passive"))
      (node (ref "C120") (pin "2") (pinfunction "2_2") (pintype "passive"))
      (node (ref "C125") (pin "2") (pinfunction "-_2") (pintype "passive"))
      (node (ref "C128") (pin "2") (pinfunction "2_2") (pintype "passive"))
      (node (ref "C129") (pin "2") (pinfunction "2_2") (pintype "passive"))
      (node (ref "C131") (pin "2") (pinfunction "-_2") (pintype "passive"))
      (node (ref "C136") (pin "2") (pinfunction "2_2") (pintype "passive"))
      (node (ref "C137") (pin "2") (pinfunction "2_2") (pintype "passive"))
      (node (ref "C138") (pin "2") (pinfunction "-_2") (pintype "passive"))
      (node (ref "C140") (pin "2") (pinfunction "-_2") (pintype "passive"))
      (node (ref "C141") (pin "2") (pinfunction "-_2") (pintype "passive"))
      (node (ref "C143") (pin "2") (pinfunction "2_2") (pintype "passive"))
      (node (ref "C144") (pin "2") (pinfunction "2_2") (pintype "passive"))
      (node (ref "C145") (pin "2") (pinfunction "2_2") (pintype "passive"))
      (node (ref "C147") (pin "2") (pinfunction "2_2") (pintype "passive"))
      (node (ref "C148") (pin "2") (pinfunction "2_2") (pintype "passive"))
      (node (ref "C150") (pin "2") (pinfunction "2_2") (pintype "passive"))
      (node (ref "C151") (pin "2") (pinfunction "2_2") (pintype "passive"))
      (node (ref "C152") (pin "2") (pinfunction "2_2") (pintype "passive"))
      (node (ref "C153") (pin "2") (pinfunction "2_2") (pintype "passive"))
      (node (ref "C154") (pin "2") (pinfunction "2_2") (pintype "passive"))
      (node (ref "C156") (pin "2") (pinfunction "2_2") (pintype "passive"))
      (node (ref "C157") (pin "2") (pinfunction "2_2") (pintype "passive"))
      (node (ref "C158") (pin "2") (pinfunction "2_2") (pintype "passive"))
      (node (ref "C159") (pin "2") (pinfunction "2_2") (pintype "passive"))
      (node (ref "C161") (pin "2") (pinfunction "2_2") (pintype "passive"))
      (node (ref "C162") (pin "2") (pinfunction "2_2") (pintype "passive"))
      (node (ref "C163") (pin "2") (pinfunction "2_2") (pintype "passive"))
      (node (ref "C164") (pin "2") (pinfunction "2_2") (pintype "passive"))
      (node (ref "C165") (pin "2") (pinfunction "-_2") (pintype "passive"))
      (node (ref "C166") (pin "2") (pinfunction "-_2") (pintype "passive"))
      (node (ref "C167") (pin "2") (pinfunction "-_2") (pintype "passive"))
      (node (ref "C168") (pin "2") (pinfunction "-_2") (pintype "passive"))
      (node (ref "C171") (pin "2") (pinfunction "-_2") (pintype "passive"))
      (node (ref "C172") (pin "1") (pinfunction "1_1") (pintype "passive"))
      (node (ref "C174") (pin "1") (pinfunction "1_1") (pintype "passive"))
      (node (ref "C175") (pin "1") (pinfunction "1_1") (pintype "passive"))
      (node (ref "C176") (pin "1") (pinfunction "1_1") (pintype "passive"))
      (node (ref "C177") (pin "1") (pinfunction "1_1") (pintype "passive"))
      (node (ref "C178") (pin "1") (pinfunction "1_1") (pintype "passive"))
      (node (ref "C179") (pin "1") (pinfunction "1_1") (pintype "passive"))
      (node (ref "C180") (pin "1") (pinfunction "1_1") (pintype "passive"))
      (node (ref "C181") (pin "1") (pinfunction "1_1") (pintype "passive"))
      (node (ref "C182") (pin "1") (pinfunction "1_1") (pintype "passive"))
      (node (ref "C183") (pin "1") (pinfunction "1_1") (pintype "passive"))
      (node (ref "C184") (pin "1") (pinfunction "1_1") (pintype "passive"))
      (node (ref "C185") (pin "1") (pinfunction "1_1") (pintype "passive"))
      (node (ref "C186") (pin "1") (pinfunction "1_1") (pintype "passive"))
      (node (ref "C187") (pin "1") (pinfunction "1_1") (pintype "passive"))
      (node (ref "C188") (pin "1") (pinfunction "1_1") (pintype "passive"))
      (node (ref "C189") (pin "1") (pinfunction "1_1") (pintype "passive"))
      (node (ref "C190") (pin "1") (pinfunction "1_1") (pintype "passive"))
      (node (ref "C191") (pin "1") (pinfunction "1_1") (pintype "passive"))
      (node (ref "C192") (pin "1") (pinfunction "1_1") (pintype "passive"))
      (node (ref "C193") (pin "1") (pinfunction "1_1") (pintype "passive"))
      (node (ref "C194") (pin "1") (pinfunction "1_1") (pintype "passive"))
      (node (ref "C196") (pin "1") (pinfunction "1_1") (pintype "passive"))
      (node (ref "C197") (pin "1") (pinfunction "1_1") (pintype "passive"))
      (node (ref "C198") (pin "1") (pinfunction "1_1") (pintype "passive"))
      (node (ref "C199") (pin "1") (pinfunction "1_1") (pintype "passive"))
      (node (ref "C200") (pin "1") (pinfunction "1_1") (pintype "passive"))
      (node (ref "C201") (pin "1") (pinfunction "1_1") (pintype "passive"))
      (node (ref "C202") (pin "1") (pinfunction "1_1") (pintype "passive"))
      (node (ref "C203") (pin "1") (pinfunction "1_1") (pintype "passive"))
      (node (ref "C204") (pin "1") (pinfunction "1_1") (pintype "passive"))
      (node (ref "C205") (pin "1") (pinfunction "1_1") (pintype "passive"))
      (node (ref "C206") (pin "1") (pinfunction "1_1") (pintype "passive"))
      (node (ref "C207") (pin "1") (pinfunction "1_1") (pintype "passive"))
      (node (ref "C208") (pin "1") (pinfunction "1_1") (pintype "passive"))
      (node (ref "C209") (pin "1") (pinfunction "1_1") (pintype "passive"))
      (node (ref "C210") (pin "1") (pinfunction "1_1") (pintype "passive"))
      (node (ref "C211") (pin "1") (pinfunction "1_1") (pintype "passive"))
      (node (ref "C212") (pin "1") (pinfunction "1_1") (pintype "passive"))
      (node (ref "C213") (pin "1") (pinfunction "1_1") (pintype "passive"))
      (node (ref "C214") (pin "1") (pinfunction "1_1") (pintype "passive"))
      (node (ref "C215") (pin "1") (pinfunction "1_1") (pintype "passive"))
      (node (ref "C216") (pin "1") (pinfunction "1_1") (pintype "passive"))
      (node (ref "C217") (pin "1") (pinfunction "1_1") (pintype "passive"))
      (node (ref "C218") (pin "1") (pinfunction "1_1") (pintype "passive"))
      (node (ref "C219") (pin "1") (pinfunction "1_1") (pintype "passive"))
      (node (ref "C220") (pin "1") (pinfunction "1_1") (pintype "passive"))
      (node (ref "C221") (pin "1") (pinfunction "1_1") (pintype "passive"))
      (node (ref "C222") (pin "1") (pinfunction "1_1") (pintype "passive"))
      (node (ref "C223") (pin "1") (pinfunction "1_1") (pintype "passive"))
      (node (ref "C224") (pin "1") (pinfunction "1_1") (pintype "passive"))
      (node (ref "C225") (pin "1") (pinfunction "1_1") (pintype "passive"))
      (node (ref "C227") (pin "1") (pinfunction "1_1") (pintype "passive"))
      (node (ref "C228") (pin "1") (pinfunction "1_1") (pintype "passive"))
      (node (ref "C229") (pin "2") (pinfunction "2_2") (pintype "passive"))
      (node (ref "C230") (pin "2") (pinfunction "2_2") (pintype "passive"))
      (node (ref "C231") (pin "2") (pinfunction "2_2") (pintype "passive"))
      (node (ref "C232") (pin "2") (pinfunction "2_2") (pintype "passive"))
      (node (ref "C233") (pin "2") (pinfunction "2_2") (pintype "passive"))
      (node (ref "C234") (pin "2") (pinfunction "2_2") (pintype "passive"))
      (node (ref "C235") (pin "2") (pinfunction "2_2") (pintype "passive"))
      (node (ref "C236") (pin "2") (pinfunction "2_2") (pintype "passive"))
      (node (ref "C237") (pin "2") (pinfunction "2_2") (pintype "passive"))
      (node (ref "C238") (pin "2") (pinfunction "2_2") (pintype "passive"))
      (node (ref "C239") (pin "2") (pinfunction "2_2") (pintype "passive"))
      (node (ref "C240") (pin "2") (pinfunction "2_2") (pintype "passive"))
      (node (ref "C241") (pin "2") (pinfunction "2_2") (pintype "passive"))
      (node (ref "C242") (pin "2") (pinfunction "2_2") (pintype "passive"))
      (node (ref "C243") (pin "2") (pinfunction "2_2") (pintype "passive"))
      (node (ref "C244") (pin "2") (pinfunction "2_2") (pintype "passive"))
      (node (ref "C245") (pin "2") (pinfunction "2_2") (pintype "passive"))
      (node (ref "C246") (pin "2") (pinfunction "2_2") (pintype "passive"))
      (node (ref "C247") (pin "2") (pinfunction "2_2") (pintype "passive"))
      (node (ref "C248") (pin "2") (pinfunction "2_2") (pintype "passive"))
      (node (ref "C249") (pin "2") (pinfunction "2_2") (pintype "passive"))
      (node (ref "C250") (pin "2") (pinfunction "2_2") (pintype "passive"))
      (node (ref "C251") (pin "2") (pinfunction "2_2") (pintype "passive"))
      (node (ref "C252") (pin "2") (pinfunction "2_2") (pintype "passive"))
      (node (ref "C254") (pin "2") (pinfunction "2_2") (pintype "passive"))
      (node (ref "C255") (pin "2") (pinfunction "2_2") (pintype "passive"))
      (node (ref "C256") (pin "2") (pinfunction "2_2") (pintype "passive"))
      (node (ref "C257") (pin "2") (pinfunction "2_2") (pintype "passive"))
      (node (ref "C258") (pin "2") (pinfunction "2_2") (pintype "passive"))
      (node (ref "C259") (pin "2") (pinfunction "2_2") (pintype "passive"))
      (node (ref "C260") (pin "2") (pinfunction "2_2") (pintype "passive"))
      (node (ref "C261") (pin "2") (pinfunction "2_2") (pintype "passive"))
      (node (ref "C262") (pin "2") (pinfunction "2_2") (pintype "passive"))
      (node (ref "C263") (pin "2") (pinfunction "2_2") (pintype "passive"))
      (node (ref "C264") (pin "2") (pinfunction "2_2") (pintype "passive"))
      (node (ref "C265") (pin "2") (pinfunction "2_2") (pintype "passive"))
      (node (ref "C266") (pin "2") (pinfunction "2_2") (pintype "passive"))
      (node (ref "C268") (pin "2") (pinfunction "2_2") (pintype "passive"))
      (node (ref "C269") (pin "2") (pinfunction "2_2") (pintype "passive"))
      (node (ref "C270") (pin "2") (pinfunction "2_2") (pintype "passive"))
      (node (ref "C271") (pin "2") (pinfunction "2_2") (pintype "passive"))
      (node (ref "C272") (pin "2") (pinfunction "2_2") (pintype "passive"))
      (node (ref "C273") (pin "2") (pinfunction "2_2") (pintype "passive"))
      (node (ref "C274") (pin "2") (pinfunction "2_2") (pintype "passive"))
      (node (ref "C276") (pin "2") (pinfunction "2_2") (pintype "passive"))
      (node (ref "C277") (pin "2") (pinfunction "2_2") (pintype "passive"))
      (node (ref "C279") (pin "2") (pinfunction "2_2") (pintype "passive"))
      (node (ref "C280") (pin "2") (pinfunction "2_2") (pintype "passive"))
      (node (ref "C281") (pin "2") (pinfunction "2_2") (pintype "passive"))
      (node (ref "C282") (pin "2") (pinfunction "2_2") (pintype "passive"))
      (node (ref "C283") (pin "2") (pinfunction "2_2") (pintype "passive"))
      (node (ref "C284") (pin "2") (pinfunction "2_2") (pintype "passive"))
      (node (ref "C285") (pin "2") (pinfunction "2_2") (pintype "passive"))
      (node (ref "C286") (pin "1") (pinfunction "1_1") (pintype "passive"))
      (node (ref "C287") (pin "1") (pinfunction "1_1") (pintype "passive"))
      (node (ref "D1") (pin "2") (pinfunction "A_2") (pintype "passive"))
      (node (ref "D2") (pin "2") (pinfunction "A_2") (pintype "passive"))
      (node (ref "D3") (pin "2") (pinfunction "A_2") (pintype "passive"))
      (node (ref "D4") (pin "1") (pinfunction "A_1") (pintype "passive"))
      (node (ref "Q4") (pin "2") (pinfunction "E_2") (pintype "passive"))
      (node (ref "R128") (pin "1") (pinfunction "1_1") (pintype "passive"))
      (node (ref "R129") (pin "1") (pinfunction "1_1") (pintype "passive"))
      (node (ref "R131") (pin "2") (pinfunction "2_2") (pintype "passive"))
      (node (ref "R132") (pin "2") (pinfunction "2_2") (pintype "passive"))
      (node (ref "R138") (pin "2") (pinfunction "2_2") (pintype "passive"))
      (node (ref "R168") (pin "1") (pinfunction "1_1") (pintype "passive"))
      (node (ref "R169") (pin "2") (pinfunction "2_2") (pintype "passive"))
      (node (ref "U11") (pin "10") (pinfunction "VSS_10") (pintype "passive"))
      (node (ref "U11") (pin "17") (pinfunction "VSS_17") (pintype "passive"))
      (node (ref "U11") (pin "21") (pinfunction "VSS_21") (pintype "passive"))
      (node (ref "U11") (pin "26") (pinfunction "VSS_26") (pintype "passive"))
      (node (ref "U11") (pin "40") (pinfunction "VSS_40") (pintype "passive"))
      (node (ref "U11") (pin "5") (pinfunction "VSS_5") (pintype "passive"))
      (node (ref "U11") (pin "55") (pinfunction "VSS_55") (pintype "passive"))
      (node (ref "U11") (pin "60") (pinfunction "VSS_60") (pintype "passive"))
      (node (ref "U11") (pin "67") (pinfunction "VSS_67") (pintype "passive"))
      (node (ref "U11") (pin "71") (pinfunction "VSS_71") (pintype "passive"))
      (node (ref "U11") (pin "76") (pinfunction "VSS_76") (pintype "passive"))
      (node (ref "U11") (pin "90") (pinfunction "VSS_90") (pintype "passive"))
      (node (ref "U15") (pin "0") (pinfunction "GND_0") (pintype "passive"))
      (node (ref "U15") (pin "3") (pinfunction "INH_3") (pintype "passive"))
      (node (ref "U15") (pin "7") (pinfunction "GND_7") (pintype "power_in"))
      (node (ref "U16") (pin "0") (pinfunction "GND_0") (pintype "passive"))
      (node (ref "U16") (pin "7") (pinfunction "GND_7") (pintype "power_in"))
      (node (ref "U17") (pin "1") (pinfunction "ADJ_1") (pintype "passive"))
      (node (ref "U34") (pin "0") (pinfunction "GND_0") (pintype "passive"))
      (node (ref "U34") (pin "7") (pinfunction "GND_7") (pintype "power_in"))
      (node (ref "U35") (pin "1") (pinfunction "GND_1") (pintype "passive"))
      (node (ref "U35") (pin "3") (pinfunction "HYST_3") (pintype "passive"))
      (node (ref "U8") (pin "A1") (pinfunction "GND_A1") (pintype "power_in"))
      (node (ref "U8") (pin "A22") (pinfunction "GND_A22") (pintype "power_in"))
      (node (ref "U8") (pin "AA13") (pinfunction "GND_AA13") (pintype "power_in"))
      (node (ref "U8") (pin "AA17") (pinfunction "GND_AA17") (pintype "power_in"))
      (node (ref "U8") (pin "AA5") (pinfunction "GND_AA5") (pintype "power_in"))
      (node (ref "U8") (pin "AA9") (pinfunction "GND_AA9") (pintype "power_in"))
      (node (ref "U8") (pin "AB1") (pinfunction "GND_AB1") (pintype "power_in"))
      (node (ref "U8") (pin "AB22") (pinfunction "GND_AB22") (pintype "power_in"))
      (node (ref "U8") (pin "B13") (pinfunction "GND_B13") (pintype "power_in"))
      (node (ref "U8") (pin "B17") (pinfunction "GND_B17") (pintype "power_in"))
      (node (ref "U8") (pin "B5") (pinfunction "GND_B5") (pintype "power_in"))
      (node (ref "U8") (pin "B9") (pinfunction "GND_B9") (pintype "power_in"))
      (node (ref "U8") (pin "D18") (pinfunction "GND_D18") (pintype "power_in"))
      (node (ref "U8") (pin "D4") (pinfunction "GND_D4") (pintype "power_in"))
      (node (ref "U8") (pin "E11") (pinfunction "GND_E11") (pintype "power_in"))
      (node (ref "U8") (pin "E15") (pinfunction "GND_E15") (pintype "power_in"))
      (node (ref "U8") (pin "E2") (pinfunction "GND_E2") (pintype "power_in"))
      (node (ref "U8") (pin "E21") (pinfunction "GND_E21") (pintype "power_in"))
      (node (ref "U8") (pin "E7") (pinfunction "GND_E7") (pintype "power_in"))
      (node (ref "U8") (pin "G18") (pinfunction "GND_G18") (pintype "power_in"))
      (node (ref "U8") (pin "G5") (pinfunction "GND_G5") (pintype "power_in"))
      (node (ref "U8") (pin "H7") (pinfunction "GND_H7") (pintype "power_in"))
      (node (ref "U8") (pin "J11") (pinfunction "GND_J11") (pintype "power_in"))
      (node (ref "U8") (pin "J13") (pinfunction "GND_J13") (pintype "power_in"))
      (node (ref "U8") (pin "J15") (pinfunction "GND_J15") (pintype "power_in"))
      (node (ref "U8") (pin "J2") (pinfunction "GND_J2") (pintype "power_in"))
      (node (ref "U8") (pin "J21") (pinfunction "GND_J21") (pintype "power_in"))
      (node (ref "U8") (pin "J9") (pinfunction "GND_J9") (pintype "power_in"))
      (node (ref "U8") (pin "K10") (pinfunction "GND_K10") (pintype "power_in"))
      (node (ref "U8") (pin "K12") (pinfunction "GND_K12") (pintype "power_in"))
      (node (ref "U8") (pin "K14") (pinfunction "GND_K14") (pintype "power_in"))
      (node (ref "U8") (pin "L11") (pinfunction "GND_L11") (pintype "power_in"))
      (node (ref "U8") (pin "L13") (pinfunction "GND_L13") (pintype "power_in"))
      (node (ref "U8") (pin "L18") (pinfunction "GND_L18") (pintype "power_in"))
      (node (ref "U8") (pin "L5") (pinfunction "GND_L5") (pintype "power_in"))
      (node (ref "U8") (pin "L9") (pinfunction "GND_L9") (pintype "power_in"))
      (node (ref "U8") (pin "M10") (pinfunction "GND_M10") (pintype "power_in"))
      (node (ref "U8") (pin "M12") (pinfunction "GND_M12") (pintype "power_in"))
      (node (ref "U8") (pin "M14") (pinfunction "GND_M14") (pintype "power_in"))
      (node (ref "U8") (pin "N11") (pinfunction "GND_N11") (pintype "power_in"))
      (node (ref "U8") (pin "N13") (pinfunction "GND_N13") (pintype "power_in"))
      (node (ref "U8") (pin "N17") (pinfunction "GND_N17") (pintype "power_in"))
      (node (ref "U8") (pin "N2") (pinfunction "GND_N2") (pintype "power_in"))
      (node (ref "U8") (pin "N21") (pinfunction "GND_N21") (pintype "power_in"))
      (node (ref "U8") (pin "N9") (pinfunction "GND_N9") (pintype "power_in"))
      (node (ref "U8") (pin "P10") (pinfunction "GND_P10") (pintype "power_in"))
      (node (ref "U8") (pin "P12") (pinfunction "GND_P12") (pintype "power_in"))
      (node (ref "U8") (pin "P14") (pinfunction "GND_P14") (pintype "power_in"))
      (node (ref "U8") (pin "R18") (pinfunction "GND_R18") (pintype "power_in"))
      (node (ref "U8") (pin "R5") (pinfunction "GND_R5") (pintype "power_in"))
      (node (ref "U8") (pin "U2") (pinfunction "GND_U2") (pintype "power_in"))
      (node (ref "U8") (pin "U21") (pinfunction "GND_U21") (pintype "power_in"))
      (node (ref "U8") (pin "U7") (pinfunction "GND_U7") (pintype "power_in"))
      (node (ref "U8") (pin "V10") (pinfunction "GND_V10") (pintype "power_in"))
      (node (ref "U8") (pin "V14") (pinfunction "GND_V14") (pintype "power_in"))
      (node (ref "U8") (pin "V4") (pinfunction "GND_V4") (pintype "power_in"))
      (node (ref "U8") (pin "W16") (pinfunction "GND_W16") (pintype "power_in"))
      (node (ref "U8") (pin "W19") (pinfunction "GND_W19") (pintype "power_in"))
      (node (ref "U8") (pin "W7") (pinfunction "GND_W7") (pintype "power_in"))
      (node (ref "U9") (pin "0") (pinfunction "GND_PAD_0") (pintype "power_in"))
      (node (ref "X17") (pin "2") (pinfunction "2_2") (pintype "passive"))
      (node (ref "X5") (pin "2") (pinfunction "2_2") (pintype "passive"))
    )
    (net (code "14") (name "Net-(C132-Pad2)") (class "Default")
      (node (ref "C132") (pin "2") (pinfunction "2_2") (pintype "passive"))
      (node (ref "R131") (pin "1") (pinfunction "1_1") (pintype "passive"))
    )
    (net (code "15") (name "Net-(C133-Pad2)") (class "Default")
      (node (ref "C133") (pin "2") (pinfunction "2_2") (pintype "passive"))
      (node (ref "R132") (pin "1") (pinfunction "1_1") (pintype "passive"))
    )
    (net (code "16") (name "Net-(C140-+)") (class "Default")
      (node (ref "C137") (pin "1") (pinfunction "1_1") (pintype "passive"))
      (node (ref "C140") (pin "1") (pinfunction "+_1") (pintype "passive"))
      (node (ref "C143") (pin "1") (pinfunction "1_1") (pintype "passive"))
      (node (ref "C144") (pin "1") (pinfunction "1_1") (pintype "passive"))
      (node (ref "C145") (pin "1") (pinfunction "1_1") (pintype "passive"))
      (node (ref "C151") (pin "1") (pinfunction "1_1") (pintype "passive"))
      (node (ref "C152") (pin "1") (pinfunction "1_1") (pintype "passive"))
      (node (ref "C153") (pin "1") (pinfunction "1_1") (pintype "passive"))
      (node (ref "L37") (pin "2") (pinfunction "2_2") (pintype "passive"))
      (node (ref "L41") (pin "1") (pinfunction "1_1") (pintype "passive"))
      (node (ref "L42") (pin "1") (pinfunction "1_1") (pintype "passive"))
      (node (ref "L43") (pin "1") (pinfunction "1_1") (pintype "passive"))
      (node (ref "R133") (pin "1") (pinfunction "1_1") (pintype "passive"))
      (node (ref "R137") (pin "1") (pinfunction "1_1") (pintype "passive"))
    )
    (net (code "17") (name "Net-(C214-Pad2)") (class "Default")
      (node (ref "C214") (pin "2") (pinfunction "2_2") (pintype "passive"))
      (node (ref "C236") (pin "1") (pinfunction "1_1") (pintype "passive"))
      (node (ref "C237") (pin "1") (pinfunction "1_1") (pintype "passive"))
      (node (ref "C238") (pin "1") (pinfunction "1_1") (pintype "passive"))
      (node (ref "C239") (pin "1") (pinfunction "1_1") (pintype "passive"))
      (node (ref "C240") (pin "1") (pinfunction "1_1") (pintype "passive"))
      (node (ref "C241") (pin "1") (pinfunction "1_1") (pintype "passive"))
      (node (ref "C242") (pin "1") (pinfunction "1_1") (pintype "passive"))
      (node (ref "C243") (pin "1") (pinfunction "1_1") (pintype "passive"))
      (node (ref "C244") (pin "1") (pinfunction "1_1") (pintype "passive"))
      (node (ref "C245") (pin "1") (pinfunction "1_1") (pintype "passive"))
      (node (ref "C280") (pin "1") (pinfunction "1_1") (pintype "passive"))
      (node (ref "C284") (pin "1") (pinfunction "1_1") (pintype "passive"))
      (node (ref "C285") (pin "1") (pinfunction "1_1") (pintype "passive"))
      (node (ref "C286") (pin "2") (pinfunction "2_2") (pintype "passive"))
      (node (ref "C287") (pin "2") (pinfunction "2_2") (pintype "passive"))
      (node (ref "Q3") (pin "2") (pinfunction "C_2") (pintype "passive"))
      (node (ref "Q3") (pin "4") (pinfunction "C_4") (pintype "passive"))
      (node (ref "U9") (pin "19") (pinfunction "VDD_1V_19") (pintype "power_in"))
      (node (ref "U9") (pin "20") (pinfunction "AVDDL_1V_20") (pintype "power_in"))
      (node (ref "U9") (pin "27") (pinfunction "AVDDL_1V_27") (pintype "power_in"))
      (node (ref "U9") (pin "30") (pinfunction "AVDDL_1V_30") (pintype "power_in"))
      (node (ref "U9") (pin "33") (pinfunction "AVDDL_1V_33") (pintype "power_in"))
      (node (ref "U9") (pin "36") (pinfunction "AVDDL_1V_36") (pintype "power_in"))
      (node (ref "U9") (pin "39") (pinfunction "AVDDL_1V_39") (pintype "power_in"))
      (node (ref "U9") (pin "48") (pinfunction "VDD_1V_48") (pintype "power_in"))
      (node (ref "U9") (pin "56") (pinfunction "VDD_1V_56") (pintype "power_in"))
      (node (ref "U9") (pin "6") (pinfunction "VDD_1V_6") (pintype "power_in"))
      (node (ref "U9") (pin "63") (pinfunction "VDD_1V_63") (pintype "power_in"))
    )
    (net (code "18") (name "Net-(C267-Pad2)") (class "Default")
      (node (ref "C267") (pin "2") (pinfunction "2_2") (pintype "passive"))
      (node (ref "R169") (pin "1") (pinfunction "1_1") (pintype "passive"))
    )
    (net (code "19") (name "Net-(C281-Pad1)") (class "Default")
      (node (ref "C281") (pin "1") (pinfunction "1_1") (pintype "passive"))
      (node (ref "C282") (pin "1") (pinfunction "1_1") (pintype "passive"))
      (node (ref "C283") (pin "1") (pinfunction "1_1") (pintype "passive"))
      (node (ref "L45") (pin "2") (pinfunction "2_2") (pintype "passive"))
      (node (ref "U9") (pin "21") (pinfunction "AVDDH_2V5_21") (pintype "power_in"))
      (node (ref "U9") (pin "31") (pinfunction "AVDDH_2V5_31") (pintype "power_in"))
    )
    (net (code "20") (name "Net-(D1-C)") (class "Default")
      (node (ref "D1") (pin "1") (pinfunction "C_1") (pintype "passive"))
      (node (ref "L36") (pin "1") (pinfunction "1_1") (pintype "passive"))
      (node (ref "U15") (pin "1") (pinfunction "OUT_1") (pintype "output"))
    )
    (net (code "21") (name "Net-(D2-C)") (class "Default")
      (node (ref "D2") (pin "1") (pinfunction "C_1") (pintype "passive"))
      (node (ref "L37") (pin "1") (pinfunction "1_1") (pintype "passive"))
      (node (ref "U16") (pin "1") (pinfunction "OUT_1") (pintype "output"))
    )
    (net (code "22") (name "Net-(D3-C)") (class "Default")
      (node (ref "D3") (pin "1") (pinfunction "C_1") (pintype "passive"))
      (node (ref "L35") (pin "1") (pinfunction "1_1") (pintype "passive"))
      (node (ref "U34") (pin "1") (pinfunction "OUT_1") (pintype "output"))
    )
    (net (code "23") (name "Net-(F1-Pad1)") (class "Default")
      (node (ref "F1") (pin "1") (pinfunction "1_1") (pintype "passive"))
      (node (ref "X5") (pin "1") (pinfunction "1_1") (pintype "passive"))
    )
    (net (code "24") (name "Net-(Q3-B)") (class "Default")
      (node (ref "Q3") (pin "1") (pinfunction "B_1") (pintype "passive"))
      (node (ref "U9") (pin "47") (pinfunction "CTRL_1V0_47") (pintype "passive"))
    )
    (net (code "25") (name "Net-(Q4-B)") (class "Default")
      (node (ref "Q4") (pin "1") (pinfunction "B_1") (pintype "passive"))
      (node (ref "R174") (pin "2") (pinfunction "2_2") (pintype "passive"))
      (node (ref "U35") (pin "5") (pinfunction "~{OT}_5") (pintype "passive"))
    )
    (net (code "26") (name "Net-(R171-Pad2)") (class "Default")
      (node (ref "R171") (pin "2") (pinfunction "2_2") (pintype "passive"))
      (node (ref "R172") (pin "2") (pinfunction "2_2") (pintype "passive"))
      (node (ref "X17") (pin "1") (pinfunction "1_1") (pintype "passive"))
    )
    (net (code "27") (name "Net-(U15-COMP)") (class "Default")
      (node (ref "C128") (pin "1") (pinfunction "1_1") (pintype "passive"))
      (node (ref "C132") (pin "1") (pinfunction "1_1") (pintype "passive"))
      (node (ref "U15") (pin "4") (pinfunction "COMP_4") (pintype "passive"))
    )
    (net (code "28") (name "Net-(U15-FB)") (class "Default")
      (node (ref "R128") (pin "2") (pinfunction "2_2") (pintype "passive"))
      (node (ref "R136") (pin "2") (pinfunction "2_2") (pintype "passive"))
      (node (ref "U15") (pin "5") (pinfunction "FB_5") (pintype "passive"))
    )
    (net (code "29") (name "Net-(U15-SYNC)") (class "Default")
      (node (ref "U15") (pin "2") (pinfunction "SYNC_2") (pintype "passive"))
      (node (ref "U16") (pin "2") (pinfunction "SYNC_2") (pintype "passive"))
      (node (ref "U34") (pin "2") (pinfunction "SYNC_2") (pintype "passive"))
    )
    (net (code "30") (name "Net-(U16-COMP)") (class "Default")
      (node (ref "C129") (pin "1") (pinfunction "1_1") (pintype "passive"))
      (node (ref "C133") (pin "1") (pinfunction "1_1") (pintype "passive"))
      (node (ref "U16") (pin "4") (pinfunction "COMP_4") (pintype "passive"))
    )
    (net (code "31") (name "Net-(U16-FB)") (class "Default")
      (node (ref "R129") (pin "2") (pinfunction "2_2") (pintype "passive"))
      (node (ref "R137") (pin "2") (pinfunction "2_2") (pintype "passive"))
      (node (ref "U16") (pin "5") (pinfunction "FB_5") (pintype "passive"))
    )
    (net (code "32") (name "Net-(U17-Vin)") (class "Default")
      (node (ref "C120") (pin "1") (pinfunction "1_1") (pintype "passive"))
      (node (ref "R133") (pin "2") (pinfunction "2_2") (pintype "passive"))
      (node (ref "U17") (pin "3") (pinfunction "Vin_3") (pintype "passive"))
    )
    (net (code "33") (name "Net-(U34-COMP)") (class "Default")
      (node (ref "C266") (pin "1") (pinfunction "1_1") (pintype "passive"))
      (node (ref "C267") (pin "1") (pinfunction "1_1") (pintype "passive"))
      (node (ref "U34") (pin "4") (pinfunction "COMP_4") (pintype "passive"))
    )
    (net (code "34") (name "Net-(U34-FB)") (class "Default")
      (node (ref "R168") (pin "2") (pinfunction "2_2") (pintype "passive"))
      (node (ref "R170") (pin "2") (pinfunction "2_2") (pintype "passive"))
      (node (ref "U34") (pin "5") (pinfunction "FB_5") (pintype "passive"))
    )
    (net (code "35") (name "Net-(U35-~{FAN}-)") (class "Default")
      (node (ref "U35") (pin "8") (pinfunction "~{FAN}-_8") (pintype "passive"))
      (node (ref "X18") (pin "2") (pinfunction "2_2") (pintype "passive"))
    )
    (net (code "36") (name "unconnected-(U8H-NC-PadAB5)") (class "Default")
      (node (ref "U8") (pin "AB5") (pinfunction "NC_AB5") (pintype "passive+no_connect"))
    )
    (net (code "37") (name "unconnected-(U8H-NC-PadE8)") (class "Default")
      (node (ref "U8") (pin "E8") (pinfunction "NC_E8") (pintype "passive+no_connect"))
    )
    (net (code "38") (name "unconnected-(U8H-NC-PadE10)") (class "Default")
      (node (ref "U8") (pin "E10") (pinfunction "NC_E10") (pintype "passive+no_connect"))
    )
    (net (code "39") (name "unconnected-(U8H-NC-PadF8)") (class "Default")
      (node (ref "U8") (pin "F8") (pinfunction "NC_F8") (pintype "passive+no_connect"))
    )
    (net (code "40") (name "unconnected-(U8H-NC-PadF9)") (class "Default")
      (node (ref "U8") (pin "F9") (pinfunction "NC_F9") (pintype "passive+no_connect"))
    )
    (net (code "41") (name "unconnected-(U8H-NC-PadF10)") (class "Default")
      (node (ref "U8") (pin "F10") (pinfunction "NC_F10") (pintype "passive+no_connect"))
    )
    (net (code "42") (name "unconnected-(U8H-NC-PadF12)") (class "Default")
      (node (ref "U8") (pin "F12") (pinfunction "NC_F12") (pintype "passive+no_connect"))
    )
    (net (code "43") (name "unconnected-(U8H-NC-PadG8)") (class "Default")
      (node (ref "U8") (pin "G8") (pinfunction "NC_G8") (pintype "passive+no_connect"))
    )
    (net (code "44") (name "unconnected-(U8H-NC-PadG9)") (class "Default")
      (node (ref "U8") (pin "G9") (pinfunction "NC_G9") (pintype "passive+no_connect"))
    )
    (net (code "45") (name "unconnected-(U8H-NC-PadG11)") (class "Default")
      (node (ref "U8") (pin "G11") (pinfunction "NC_G11") (pintype "passive+no_connect"))
    )
    (net (code "46") (name "unconnected-(U8H-NC-PadH10)") (class "Default")
      (node (ref "U8") (pin "H10") (pinfunction "NC_H10") (pintype "passive+no_connect"))
    )
    (net (code "47") (name "unconnected-(U8H-NC-PadH11)") (class "Default")
      (node (ref "U8") (pin "H11") (pinfunction "NC_H11") (pintype "passive+no_connect"))
    )
    (net (code "48") (name "unconnected-(U8H-NC-PadH12)") (class "Default")
      (node (ref "U8") (pin "H12") (pinfunction "NC_H12") (pintype "passive+no_connect"))
    )
    (net (code "49") (name "unconnected-(U8H-NC-PadR7)") (class "Default")
      (node (ref "U8") (pin "R7") (pinfunction "NC_R7") (pintype "passive+no_connect"))
    )
    (net (code "50") (name "unconnected-(U8H-NC-PadR8)") (class "Default")
      (node (ref "U8") (pin "R8") (pinfunction "NC_R8") (pintype "passive+no_connect"))
    )
    (net (code "51") (name "unconnected-(U8H-NC-PadR9)") (class "Default")
      (node (ref "U8") (pin "R9") (pinfunction "NC_R9") (pintype "passive+no_connect"))
    )
    (net (code "52") (name "unconnected-(U8H-NC-PadR11)") (class "Default")
      (node (ref "U8") (pin "R11") (pinfunction "NC_R11") (pintype "passive+no_connect"))
    )
    (net (code "53") (name "unconnected-(U8H-NC-PadR13)") (class "Default")
      (node (ref "U8") (pin "R13") (pinfunction "NC_R13") (pintype "passive+no_connect"))
    )
    (net (code "54") (name "unconnected-(U8H-NC-PadR15)") (class "Default")
      (node (ref "U8") (pin "R15") (pinfunction "NC_R15") (pintype "passive+no_connect"))
    )
    (net (code "55") (name "unconnected-(U8H-NC-PadR16)") (class "Default")
      (node (ref "U8") (pin "R16") (pinfunction "NC_R16") (pintype "passive+no_connect"))
    )
    (net (code "56") (name "unconnected-(U8H-NC-PadT7)") (class "Default")
      (node (ref "U8") (pin "T7") (pinfunction "NC_T7") (pintype "passive+no_connect"))
    )
    (net (code "57") (name "unconnected-(U8H-NC-PadT8)") (class "Default")
      (node (ref "U8") (pin "T8") (pinfunction "NC_T8") (pintype "passive+no_connect"))
    )
    (net (code "58") (name "unconnected-(U8H-NC-PadT10)") (class "Default")
      (node (ref "U8") (pin "T10") (pinfunction "NC_T10") (pintype "passive+no_connect"))
    )
    (net (code "59") (name "unconnected-(U8H-NC-PadT11)") (class "Default")
      (node (ref "U8") (pin "T11") (pinfunction "NC_T11") (pintype "passive+no_connect"))
    )
    (net (code "60") (name "unconnected-(U8H-NC-PadT12)") (class "Default")
      (node (ref "U8") (pin "T12") (pinfunction "NC_T12") (pintype "passive+no_connect"))
    )
    (net (code "61") (name "unconnected-(U8H-NC-PadT14)") (class "Default")
      (node (ref "U8") (pin "T14") (pinfunction "NC_T14") (pintype "passive+no_connect"))
    )
    (net (code "62") (name "unconnected-(U8H-NC-PadT15)") (class "Default")
      (node (ref "U8") (pin "T15") (pinfunction "NC_T15") (pintype "passive+no_connect"))
    )
    (net (code "63") (name "unconnected-(U8H-NC-PadT16)") (class "Default")
      (node (ref "U8") (pin "T16") (pinfunction "NC_T16") (pintype "passive+no_connect"))
    )
    (net (code "64") (name "unconnected-(U8H-NC-PadU6)") (class "Default")
      (node (ref "U8") (pin "U6") (pinfunction "NC_U6") (pintype "passive+no_connect"))
    )
    (net (code "65") (name "unconnected-(U8H-NC-PadU8)") (class "Default")
      (node (ref "U8") (pin "U8") (pinfunction "NC_U8") (pintype "passive+no_connect"))
    )
    (net (code "66") (name "unconnected-(U8H-NC-PadU9)") (class "Default")
      (node (ref "U8") (pin "U9") (pinfunction "NC_U9") (pintype "passive+no_connect"))
    )
    (net (code "67") (name "unconnected-(U8H-NC-PadU10)") (class "Default")
      (node (ref "U8") (pin "U10") (pinfunction "NC_U10") (pintype "passive+no_connect"))
    )
    (net (code "68") (name "unconnected-(U8H-NC-PadU12)") (class "Default")
      (node (ref "U8") (pin "U12") (pinfunction "NC_U12") (pintype "passive+no_connect"))
    )
    (net (code "69") (name "unconnected-(U8H-NC-PadU16)") (class "Default")
      (node (ref "U8") (pin "U16") (pinfunction "NC_U16") (pintype "passive+no_connect"))
    )
    (net (code "70") (name "unconnected-(U8H-NC-PadU17)") (class "Default")
      (node (ref "U8") (pin "U17") (pinfunction "NC_U17") (pintype "passive+no_connect"))
    )
    (net (code "71") (name "unconnected-(U8H-NC-PadV5)") (class "Default")
      (node (ref "U8") (pin "V5") (pinfunction "NC_V5") (pintype "passive+no_connect"))
    )
    (net (code "72") (name "unconnected-(U8H-NC-PadV7)") (class "Default")
      (node (ref "U8") (pin "V7") (pinfunction "NC_V7") (pintype "passive+no_connect"))
    )
    (net (code "73") (name "unconnected-(U8H-NC-PadV9)") (class "Default")
      (node (ref "U8") (pin "V9") (pinfunction "NC_V9") (pintype "passive+no_connect"))
    )
    (net (code "74") (name "unconnected-(U8H-NC-PadV13)") (class "Default")
      (node (ref "U8") (pin "V13") (pinfunction "NC_V13") (pintype "passive+no_connect"))
    )
    (net (code "75") (name "unconnected-(U8H-NC-PadV17)") (class "Default")
      (node (ref "U8") (pin "V17") (pinfunction "NC_V17") (pintype "passive+no_connect"))
    )
    (net (code "76") (name "unconnected-(U8H-NC-PadV18)") (class "Default")
      (node (ref "U8") (pin "V18") (pinfunction "NC_V18") (pintype "passive+no_connect"))
    )
    (net (code "77") (name "unconnected-(U8H-NC-PadV19)") (class "Default")
      (node (ref "U8") (pin "V19") (pinfunction "NC_V19") (pintype "passive+no_connect"))
    )
    (net (code "78") (name "unconnected-(U8H-NC-PadW6)") (class "Default")
      (node (ref "U8") (pin "W6") (pinfunction "NC_W6") (pintype "passive+no_connect"))
    )
    (net (code "79") (name "unconnected-(U8H-NC-PadW8)") (class "Default")
      (node (ref "U8") (pin "W8") (pinfunction "NC_W8") (pintype "passive+no_connect"))
    )
    (net (code "80") (name "unconnected-(U8H-NC-PadW9)") (class "Default")
      (node (ref "U8") (pin "W9") (pinfunction "NC_W9") (pintype "passive+no_connect"))
    )
    (net (code "81") (name "unconnected-(U8H-NC-PadW10)") (class "Default")
      (node (ref "U8") (pin "W10") (pinfunction "NC_W10") (pintype "passive+no_connect"))
    )
    (net (code "82") (name "unconnected-(U8H-NC-PadW13)") (class "Default")
      (node (ref "U8") (pin "W13") (pinfunction "NC_W13") (pintype "passive+no_connect"))
    )
    (net (code "83") (name "unconnected-(U8H-NC-PadW14)") (class "Default")
      (node (ref "U8") (pin "W14") (pinfunction "NC_W14") (pintype "passive+no_connect"))
    )
    (net (code "84") (name "unconnected-(U8H-NC-PadW15)") (class "Default")
      (node (ref "U8") (pin "W15") (pinfunction "NC_W15") (pintype "passive+no_connect"))
    )
    (net (code "85") (name "unconnected-(U8H-NC-PadW17)") (class "Default")
      (node (ref "U8") (pin "W17") (pinfunction "NC_W17") (pintype "passive+no_connect"))
    )
    (net (code "86") (name "unconnected-(U8H-NC-PadW18)") (class "Default")
      (node (ref "U8") (pin "W18") (pinfunction "NC_W18") (pintype "passive+no_connect"))
    )
    (net (code "87") (name "unconnected-(U8H-NC-PadY5)") (class "Default")
      (node (ref "U8") (pin "Y5") (pinfunction "NC_Y5") (pintype "passive+no_connect"))
    )
    (net (code "88") (name "unconnected-(U8H-NC-PadY6)") (class "Default")
      (node (ref "U8") (pin "Y6") (pinfunction "NC_Y6") (pintype "passive+no_connect"))
    )
    (net (code "89") (name "unconnected-(U8H-NC-PadY8)") (class "Default")
      (node (ref "U8") (pin "Y8") (pinfunction "NC_Y8") (pintype "passive+no_connect"))
    )
    (net (code "90") (name "unconnected-(U8H-NC-PadY10)") (class "Default")
      (node (ref "U8") (pin "Y10") (pinfunction "NC_Y10") (pintype "passive+no_connect"))
    )
    (net (code "91") (name "unconnected-(U8H-NC-PadY14)") (class "Default")
      (node (ref "U8") (pin "Y14") (pinfunction "NC_Y14") (pintype "passive+no_connect"))
    )
    (net (code "92") (name "unconnected-(U8H-NC-PadY16)") (class "Default")
      (node (ref "U8") (pin "Y16") (pinfunction "NC_Y16") (pintype "passive+no_connect"))
    )
    (net (code "93") (name "unconnected-(U8H-NC-PadY18)") (class "Default")
      (node (ref "U8") (pin "Y18") (pinfunction "NC_Y18") (pintype "passive+no_connect"))
    )
    (net (code "94") (name "unconnected-(U9E-CTRL_2V5-Pad46)") (class "Default")
      (node (ref "U9") (pin "46") (pinfunction "CTRL_2V5_46") (pintype "passive+no_connect"))
    )
    (net (code "95") (name "unconnected-(U9E-NC-Pad7)") (class "Default")
      (node (ref "U9") (pin "7") (pinfunction "NC_7") (pintype "passive+no_connect"))
    )
    (net (code "96") (name "unconnected-(U9E-NC-Pad8)") (class "Default")
      (node (ref "U9") (pin "8") (pinfunction "NC_8") (pintype "passive+no_connect"))
    )
    (net (code "97") (name "unconnected-(U9E-NC-Pad9)") (class "Default")
      (node (ref "U9") (pin "9") (pinfunction "NC_9") (pintype "passive+no_connect"))
    )
    (net (code "98") (name "unconnected-(U9E-NC-Pad10)") (class "Default")
      (node (ref "U9") (pin "10") (pinfunction "NC_10") (pintype "passive+no_connect"))
    )
    (net (code "99") (name "unconnected-(U9E-NC-Pad11)") (class "Default")
      (node (ref "U9") (pin "11") (pinfunction "NC_11") (pintype "passive+no_connect"))
    )
    (net (code "100") (name "unconnected-(U11B-NC-Pad14)") (class "Default")
      (node (ref "U11") (pin "14") (pinfunction "NC_14") (pintype "passive+no_connect"))
    )
    (net (code "101") (name "unconnected-(U11B-NC-Pad16)") (class "Default")
      (node (ref "U11") (pin "16") (pinfunction "NC_16") (pintype "passive+no_connect"))
    )
    (net (code "102") (name "unconnected-(U11B-NC-Pad66)") (class "Default")
      (node (ref "U11") (pin "66") (pinfunction "NC_66") (pintype "passive+no_connect"))
    )
    (net (code "103") (name "unconnected-(U15-VREF-Pad6)") (class "Default")
      (node (ref "U15") (pin "6") (pinfunction "VREF_6") (pintype "power_in+no_connect"))
    )
    (net (code "104") (name "unconnected-(U16-VREF-Pad6)") (class "Default")
      (node (ref "U16") (pin "6") (pinfunction "VREF_6") (pintype "power_in+no_connect"))
    )
    (net (code "105") (name "unconnected-(U34-VREF-Pad6)") (class "Default")
      (node (ref "U34") (pin "6") (pinfunction "VREF_6") (pintype "power_in+no_connect"))
    )
  )
)
